# veils_v40.net
KiCad netlist of a schematic drawn in EAGLE
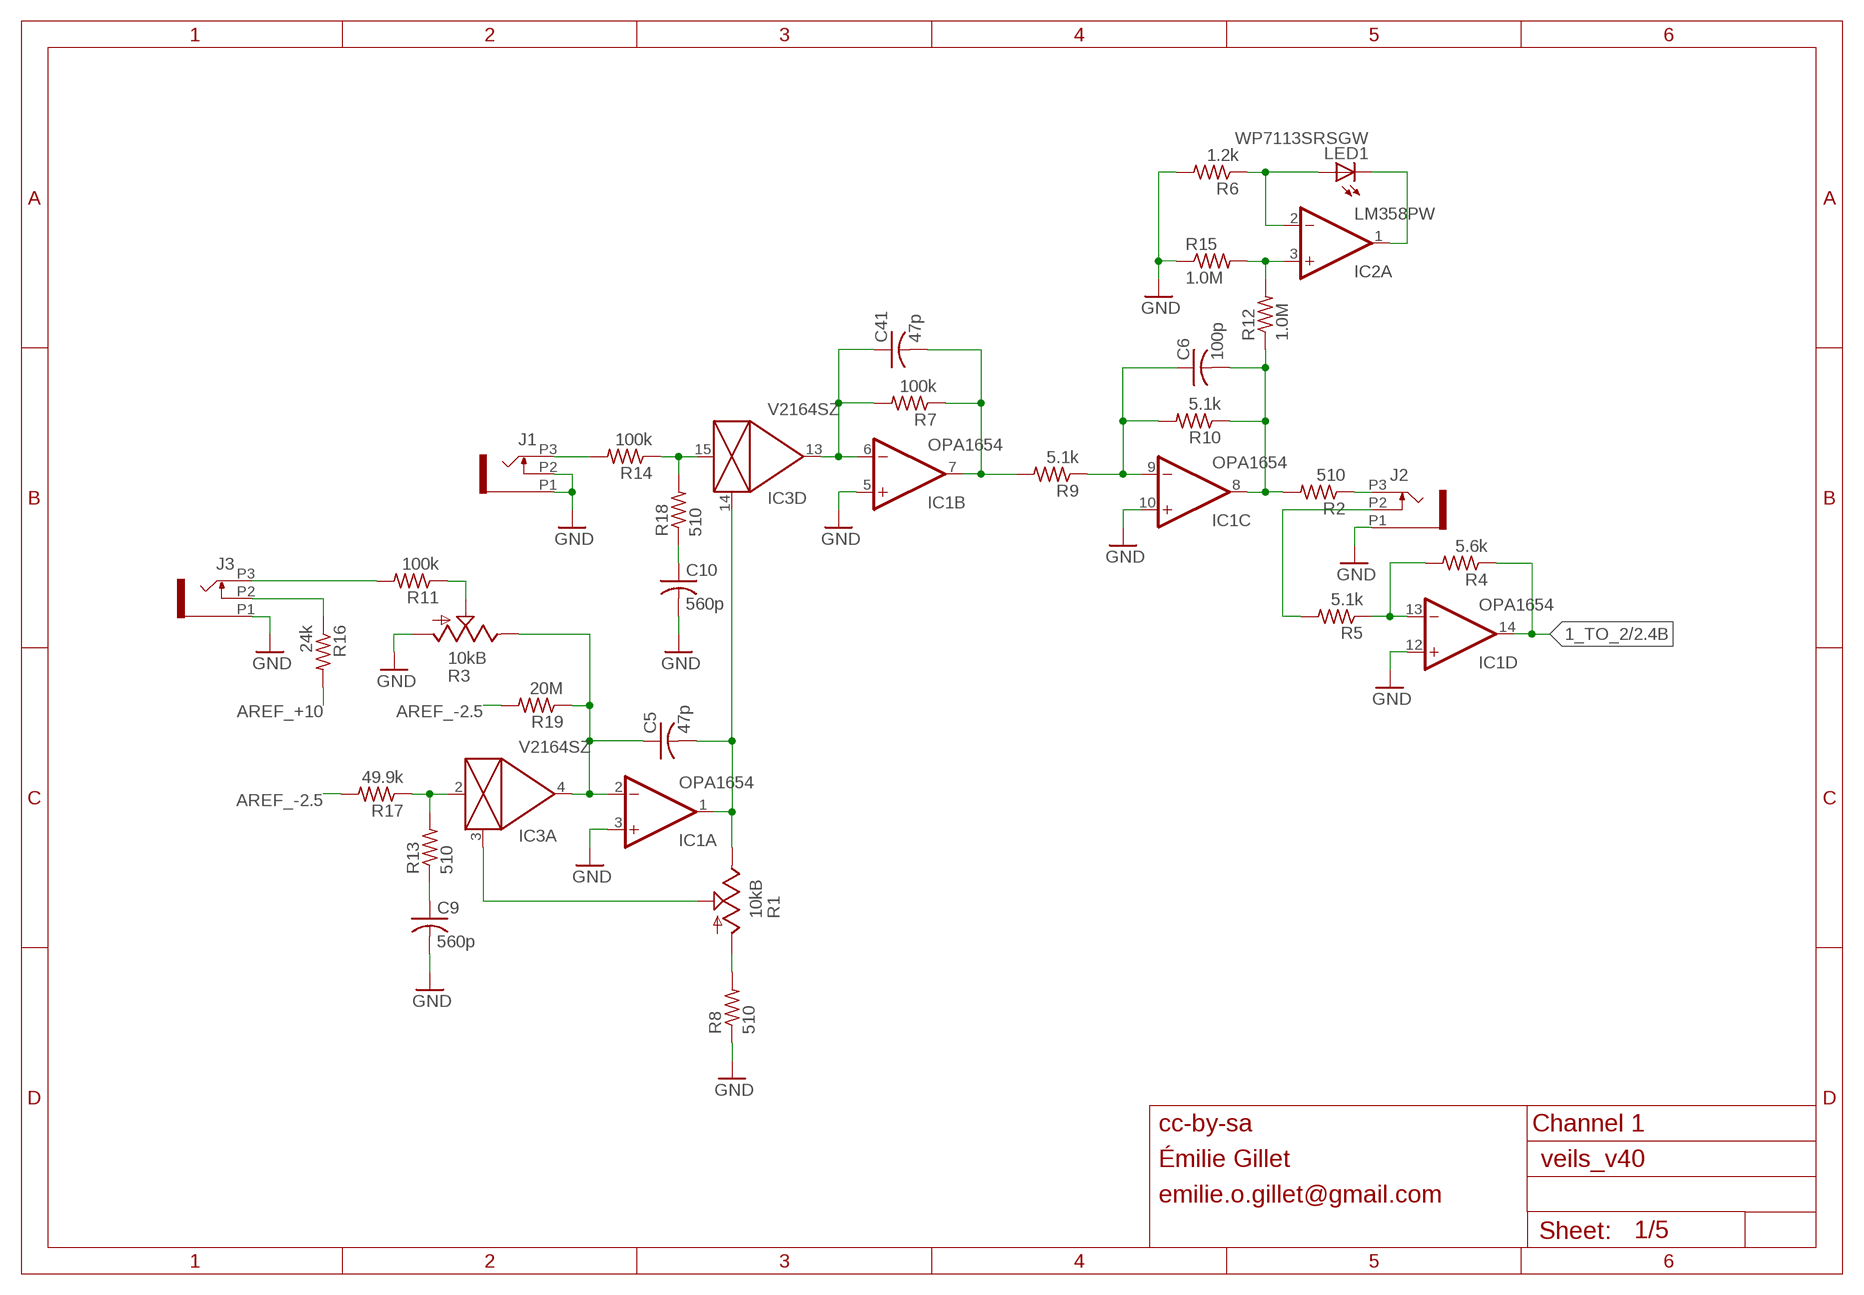
[diagram p0: schematic, sheet 1]
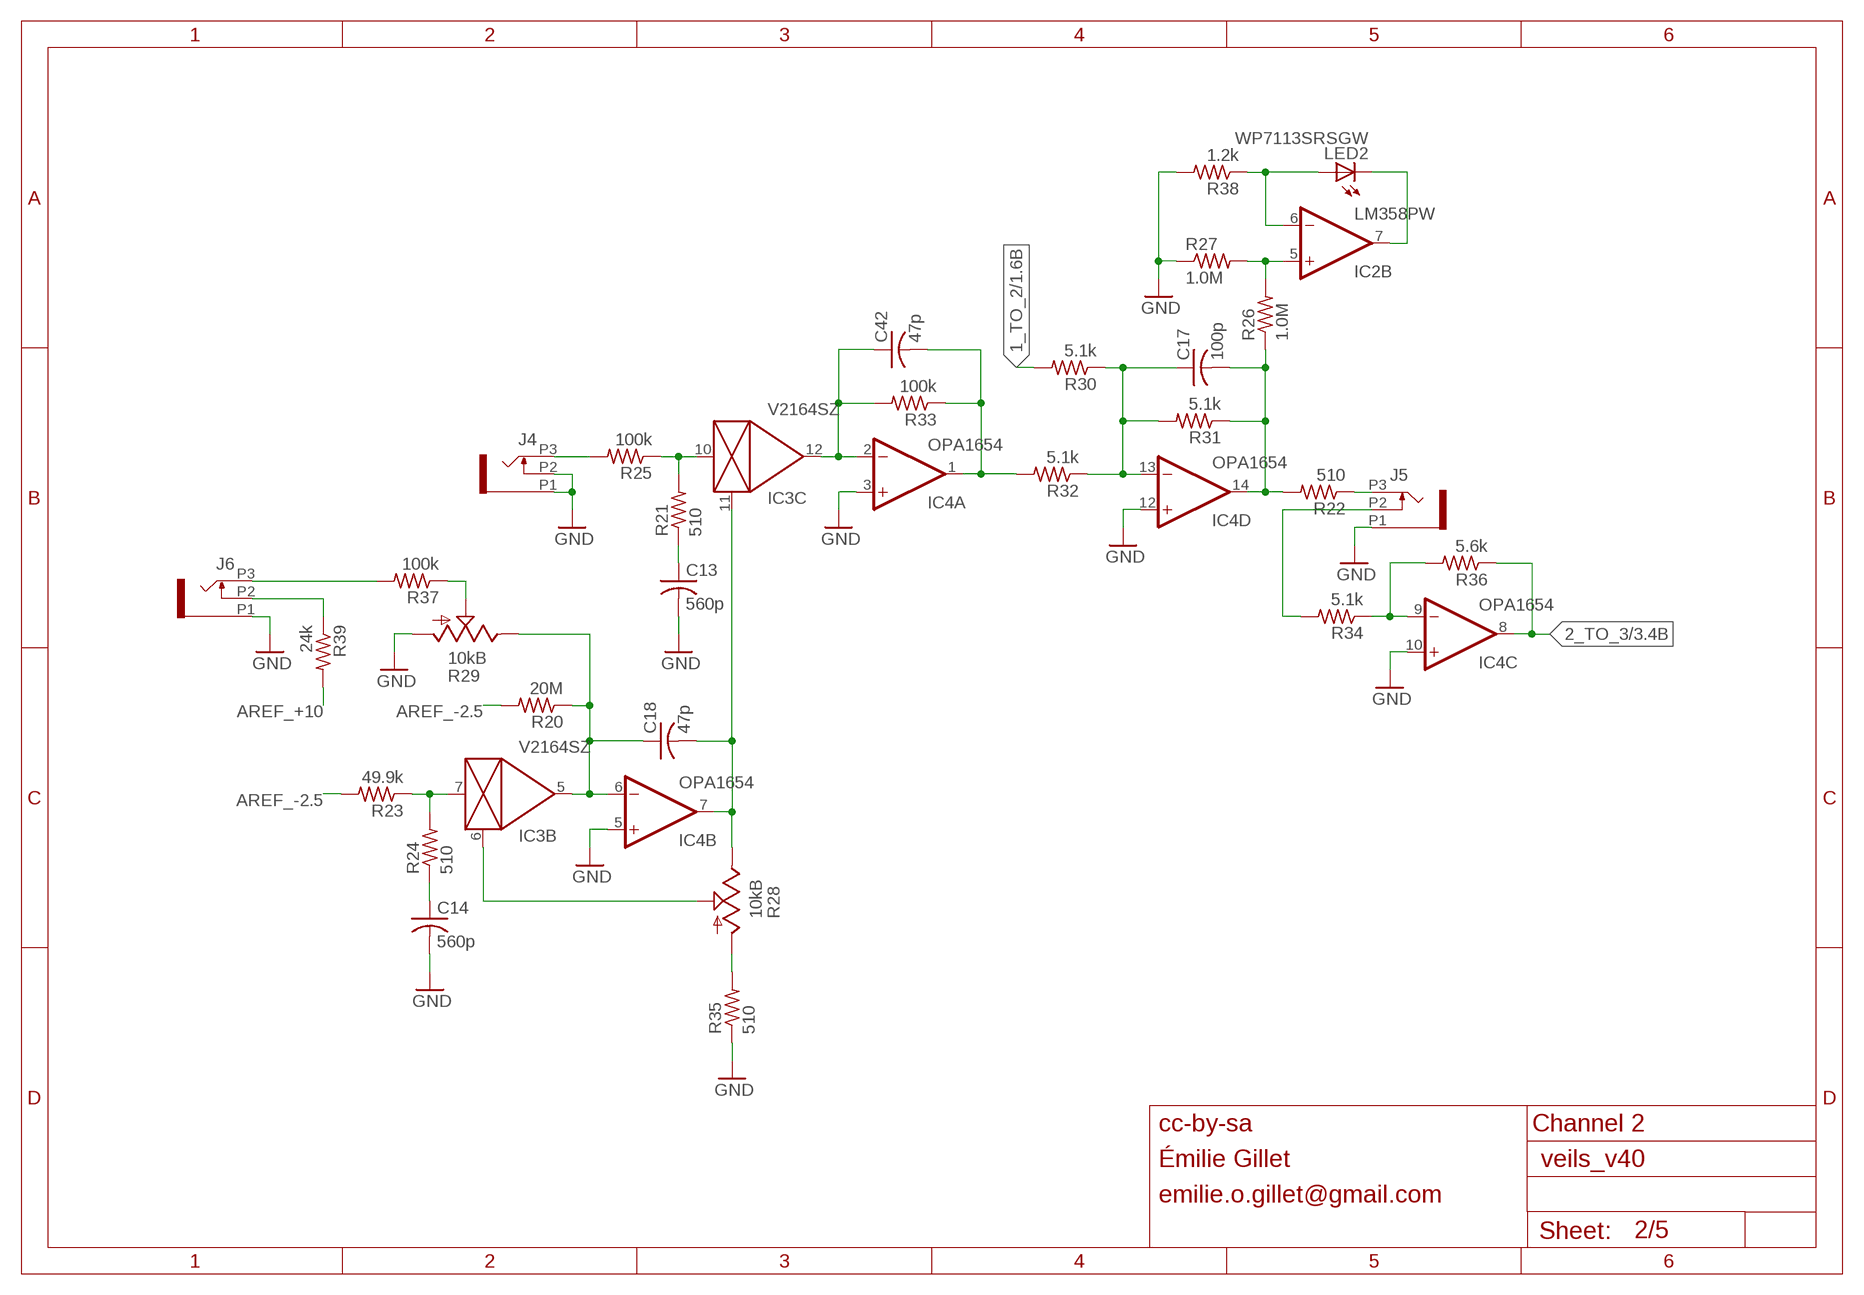
[diagram p1: schematic, sheet 2]
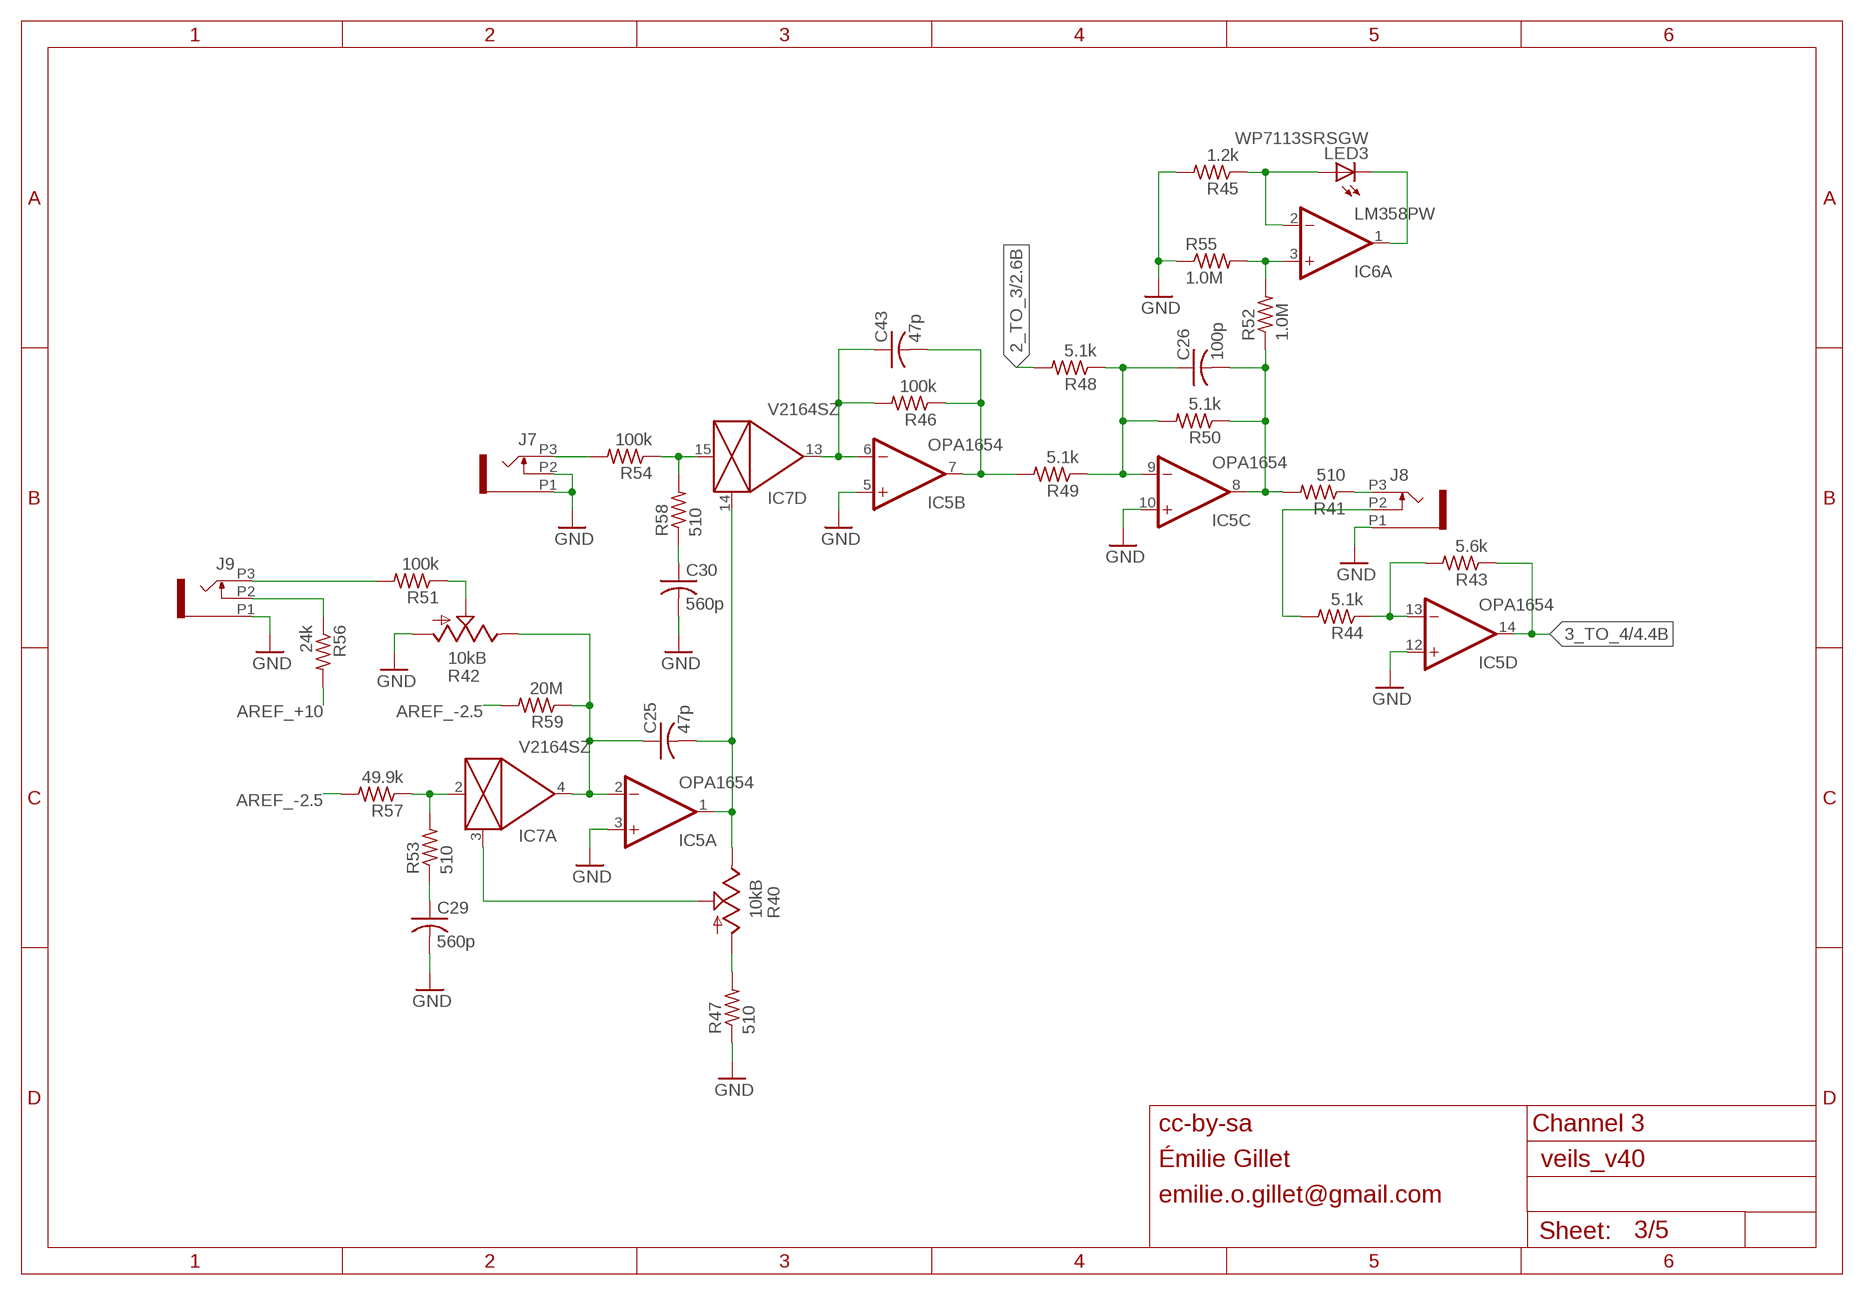
[diagram p2: schematic, sheet 3]
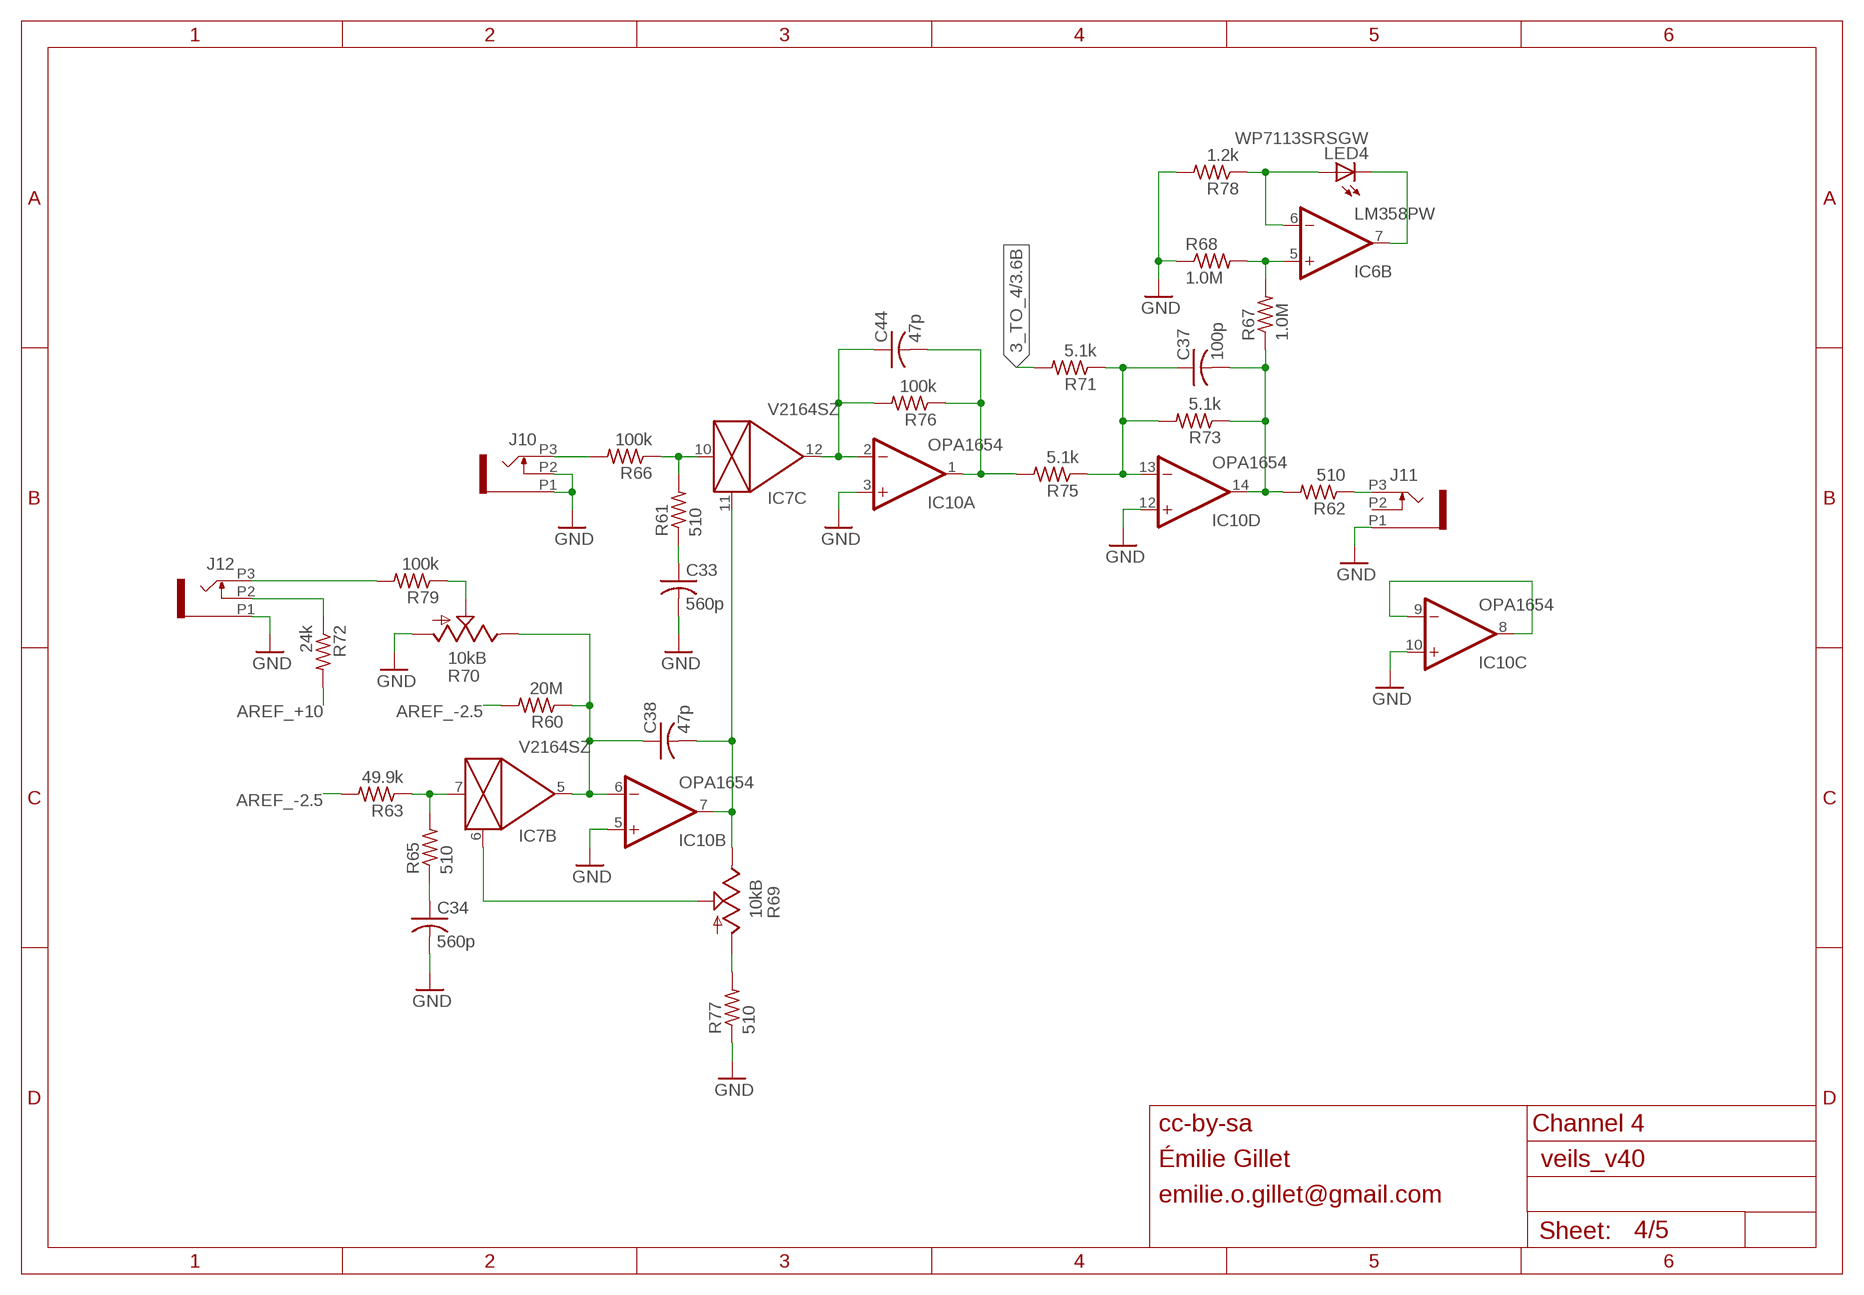
[diagram p3: schematic, sheet 4]
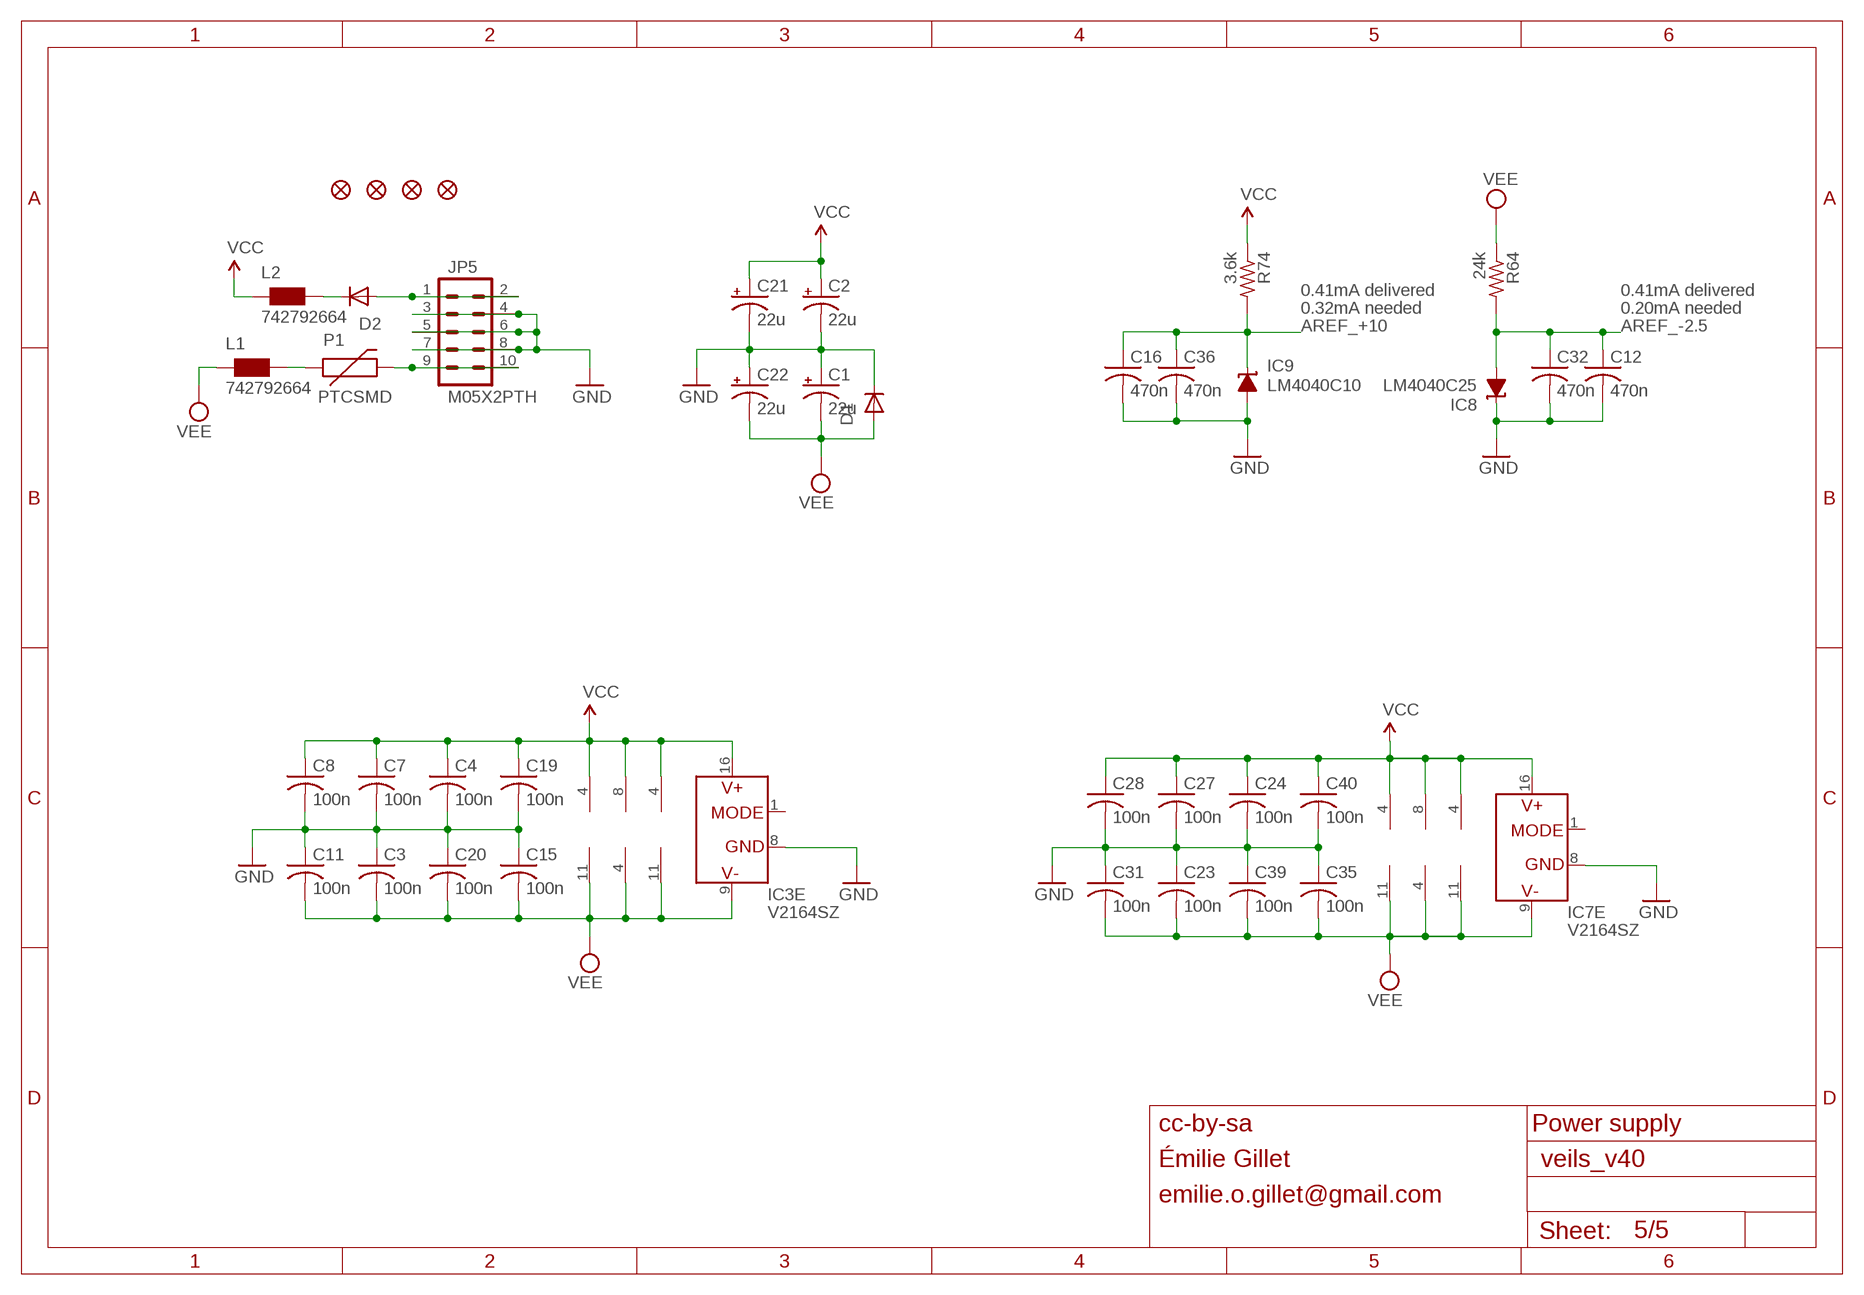
[diagram p4: schematic, sheet 5]

(export (version "E")
  (design (tool "Eeschema 10.0.6"))
  (components
    (comp (ref "C25")
      (value "47p")
      (footprint "eagle-import:C0402")
      (libsource (lib "eagle-import") (part "C-USC0402"))
    )
    (comp (ref "C26")
      (value "100p")
      (footprint "eagle-import:C0402")
      (libsource (lib "eagle-import") (part "C-USC0402"))
    )
    (comp (ref "C29")
      (value "560p")
      (footprint "eagle-import:C0402")
      (libsource (lib "eagle-import") (part "C-USC0402"))
    )
    (comp (ref "C30")
      (value "560p")
      (footprint "eagle-import:C0402")
      (libsource (lib "eagle-import") (part "C-USC0402"))
    )
    (comp (ref "C43")
      (value "47p")
      (footprint "eagle-import:C0402")
      (libsource (lib "eagle-import") (part "C-USC0402"))
    )
    (comp (ref "IC5")
      (value "OPA1654")
      (footprint "eagle-import:TSSOP14")
      (libsource (lib "eagle-import") (part "TL074PW"))
    )
    (comp (ref "IC6")
      (value "LM358PW")
      (footprint "eagle-import:TSSOP8")
      (libsource (lib "eagle-import") (part "TL072PW"))
    )
    (comp (ref "IC7")
      (value "V2164SZ")
      (footprint "eagle-import:SOIC16N")
      (libsource (lib "eagle-import") (part "SSM2164S"))
    )
    (comp (ref "J7")
      (value "PJ301_THONKICONN6")
      (footprint "eagle-import:WQP_PJ_301M6")
      (libsource (lib "eagle-import") (part "PJ301_THONKICONN6"))
    )
    (comp (ref "J8")
      (value "PJ301_THONKICONN6")
      (footprint "eagle-import:WQP_PJ_301M6")
      (libsource (lib "eagle-import") (part "PJ301_THONKICONN6"))
    )
    (comp (ref "J9")
      (value "PJ301_THONKICONN6")
      (footprint "eagle-import:WQP_PJ_301M6")
      (libsource (lib "eagle-import") (part "PJ301_THONKICONN6"))
    )
    (comp (ref "LED3")
      (value "WP7113SRSGW")
      (footprint "eagle-import:LED5MM")
      (libsource (lib "eagle-import") (part "LED5MM"))
    )
    (comp (ref "R40")
      (value "10kB")
      (footprint "eagle-import:ALPS_POT_VERTICAL")
      (libsource (lib "eagle-import") (part "POT_USVERTICAL"))
    )
    (comp (ref "R41")
      (value "510")
      (footprint "eagle-import:R0402")
      (libsource (lib "eagle-import") (part "R-US_R0402"))
    )
    (comp (ref "R42")
      (value "10kB")
      (footprint "eagle-import:ALPS_POT_VERTICAL_PS")
      (libsource (lib "eagle-import") (part "pot-alps_POT_USVERTICAL_PS"))
    )
    (comp (ref "R43")
      (value "5.6k")
      (footprint "eagle-import:R0402")
      (libsource (lib "eagle-import") (part "R-US_R0402"))
    )
    (comp (ref "R44")
      (value "5.1k")
      (footprint "eagle-import:R0402")
      (libsource (lib "eagle-import") (part "R-US_R0402"))
    )
    (comp (ref "R45")
      (value "1.2k")
      (footprint "eagle-import:R0402")
      (libsource (lib "eagle-import") (part "R-US_R0402"))
    )
    (comp (ref "R46")
      (value "100k")
      (footprint "eagle-import:R0402")
      (libsource (lib "eagle-import") (part "R-US_R0402"))
    )
    (comp (ref "R47")
      (value "510")
      (footprint "eagle-import:R0402")
      (libsource (lib "eagle-import") (part "R-US_R0402"))
    )
    (comp (ref "R48")
      (value "5.1k")
      (footprint "eagle-import:R0402")
      (libsource (lib "eagle-import") (part "R-US_R0402"))
    )
    (comp (ref "R49")
      (value "5.1k")
      (footprint "eagle-import:R0402")
      (libsource (lib "eagle-import") (part "R-US_R0402"))
    )
    (comp (ref "R50")
      (value "5.1k")
      (footprint "eagle-import:R0402")
      (libsource (lib "eagle-import") (part "R-US_R0402"))
    )
    (comp (ref "R51")
      (value "100k")
      (footprint "eagle-import:R0402")
      (libsource (lib "eagle-import") (part "R-US_R0402"))
    )
    (comp (ref "R52")
      (value "1.0M")
      (footprint "eagle-import:R0402")
      (libsource (lib "eagle-import") (part "R-US_R0402"))
    )
    (comp (ref "R53")
      (value "510")
      (footprint "eagle-import:R0402")
      (libsource (lib "eagle-import") (part "R-US_R0402"))
    )
    (comp (ref "R54")
      (value "100k")
      (footprint "eagle-import:R0402")
      (libsource (lib "eagle-import") (part "R-US_R0402"))
    )
    (comp (ref "R55")
      (value "1.0M")
      (footprint "eagle-import:R0402")
      (libsource (lib "eagle-import") (part "R-US_R0402"))
    )
    (comp (ref "R56")
      (value "24k")
      (footprint "eagle-import:R0402")
      (libsource (lib "eagle-import") (part "R-US_R0402"))
    )
    (comp (ref "R57")
      (value "49.9k")
      (footprint "eagle-import:R0402")
      (libsource (lib "eagle-import") (part "R-US_R0402"))
    )
    (comp (ref "R58")
      (value "510")
      (footprint "eagle-import:R0402")
      (libsource (lib "eagle-import") (part "R-US_R0402"))
    )
    (comp (ref "R59")
      (value "20M")
      (footprint "eagle-import:R0402")
      (libsource (lib "eagle-import") (part "R-US_R0402"))
    )
    (comp (ref "C33")
      (value "560p")
      (footprint "eagle-import:C0402")
      (libsource (lib "eagle-import") (part "C-USC0402"))
    )
    (comp (ref "C34")
      (value "560p")
      (footprint "eagle-import:C0402")
      (libsource (lib "eagle-import") (part "C-USC0402"))
    )
    (comp (ref "C37")
      (value "100p")
      (footprint "eagle-import:C0402")
      (libsource (lib "eagle-import") (part "C-USC0402"))
    )
    (comp (ref "C38")
      (value "47p")
      (footprint "eagle-import:C0402")
      (libsource (lib "eagle-import") (part "C-USC0402"))
    )
    (comp (ref "C44")
      (value "47p")
      (footprint "eagle-import:C0402")
      (libsource (lib "eagle-import") (part "C-USC0402"))
    )
    (comp (ref "IC10")
      (value "OPA1654")
      (footprint "eagle-import:TSSOP14")
      (libsource (lib "eagle-import") (part "TL074PW"))
    )
    (comp (ref "J10")
      (value "PJ301_THONKICONN6")
      (footprint "eagle-import:WQP_PJ_301M6")
      (libsource (lib "eagle-import") (part "PJ301_THONKICONN6"))
    )
    (comp (ref "J11")
      (value "PJ301_THONKICONN6")
      (footprint "eagle-import:WQP_PJ_301M6")
      (libsource (lib "eagle-import") (part "PJ301_THONKICONN6"))
    )
    (comp (ref "J12")
      (value "PJ301_THONKICONN6")
      (footprint "eagle-import:WQP_PJ_301M6")
      (libsource (lib "eagle-import") (part "PJ301_THONKICONN6"))
    )
    (comp (ref "LED4")
      (value "WP7113SRSGW")
      (footprint "eagle-import:LED5MM")
      (libsource (lib "eagle-import") (part "LED5MM"))
    )
    (comp (ref "R60")
      (value "20M")
      (footprint "eagle-import:R0402")
      (libsource (lib "eagle-import") (part "R-US_R0402"))
    )
    (comp (ref "R61")
      (value "510")
      (footprint "eagle-import:R0402")
      (libsource (lib "eagle-import") (part "R-US_R0402"))
    )
    (comp (ref "R62")
      (value "510")
      (footprint "eagle-import:R0402")
      (libsource (lib "eagle-import") (part "R-US_R0402"))
    )
    (comp (ref "R63")
      (value "49.9k")
      (footprint "eagle-import:R0402")
      (libsource (lib "eagle-import") (part "R-US_R0402"))
    )
    (comp (ref "R65")
      (value "510")
      (footprint "eagle-import:R0402")
      (libsource (lib "eagle-import") (part "R-US_R0402"))
    )
    (comp (ref "R66")
      (value "100k")
      (footprint "eagle-import:R0402")
      (libsource (lib "eagle-import") (part "R-US_R0402"))
    )
    (comp (ref "R67")
      (value "1.0M")
      (footprint "eagle-import:R0402")
      (libsource (lib "eagle-import") (part "R-US_R0402"))
    )
    (comp (ref "R68")
      (value "1.0M")
      (footprint "eagle-import:R0402")
      (libsource (lib "eagle-import") (part "R-US_R0402"))
    )
    (comp (ref "R69")
      (value "10kB")
      (footprint "eagle-import:ALPS_POT_VERTICAL")
      (libsource (lib "eagle-import") (part "POT_USVERTICAL"))
    )
    (comp (ref "R70")
      (value "10kB")
      (footprint "eagle-import:ALPS_POT_VERTICAL_PS")
      (libsource (lib "eagle-import") (part "pot-alps_POT_USVERTICAL_PS"))
    )
    (comp (ref "R71")
      (value "5.1k")
      (footprint "eagle-import:R0402")
      (libsource (lib "eagle-import") (part "R-US_R0402"))
    )
    (comp (ref "R72")
      (value "24k")
      (footprint "eagle-import:R0402")
      (libsource (lib "eagle-import") (part "R-US_R0402"))
    )
    (comp (ref "R73")
      (value "5.1k")
      (footprint "eagle-import:R0402")
      (libsource (lib "eagle-import") (part "R-US_R0402"))
    )
    (comp (ref "R75")
      (value "5.1k")
      (footprint "eagle-import:R0402")
      (libsource (lib "eagle-import") (part "R-US_R0402"))
    )
    (comp (ref "R76")
      (value "100k")
      (footprint "eagle-import:R0402")
      (libsource (lib "eagle-import") (part "R-US_R0402"))
    )
    (comp (ref "R77")
      (value "510")
      (footprint "eagle-import:R0402")
      (libsource (lib "eagle-import") (part "R-US_R0402"))
    )
    (comp (ref "R78")
      (value "1.2k")
      (footprint "eagle-import:R0402")
      (libsource (lib "eagle-import") (part "R-US_R0402"))
    )
    (comp (ref "R79")
      (value "100k")
      (footprint "eagle-import:R0402")
      (libsource (lib "eagle-import") (part "R-US_R0402"))
    )
    (comp (ref "C13")
      (value "560p")
      (footprint "eagle-import:C0402")
      (libsource (lib "eagle-import") (part "C-USC0402"))
    )
    (comp (ref "C14")
      (value "560p")
      (footprint "eagle-import:C0402")
      (libsource (lib "eagle-import") (part "C-USC0402"))
    )
    (comp (ref "C17")
      (value "100p")
      (footprint "eagle-import:C0402")
      (libsource (lib "eagle-import") (part "C-USC0402"))
    )
    (comp (ref "C18")
      (value "47p")
      (footprint "eagle-import:C0402")
      (libsource (lib "eagle-import") (part "C-USC0402"))
    )
    (comp (ref "C42")
      (value "47p")
      (footprint "eagle-import:C0402")
      (libsource (lib "eagle-import") (part "C-USC0402"))
    )
    (comp (ref "IC2")
      (value "LM358PW")
      (footprint "eagle-import:TSSOP8")
      (libsource (lib "eagle-import") (part "TL072PW"))
    )
    (comp (ref "IC3")
      (value "V2164SZ")
      (footprint "eagle-import:SOIC16N")
      (libsource (lib "eagle-import") (part "SSM2164S"))
    )
    (comp (ref "IC4")
      (value "OPA1654")
      (footprint "eagle-import:TSSOP14")
      (libsource (lib "eagle-import") (part "TL074PW"))
    )
    (comp (ref "J4")
      (value "PJ301_THONKICONN6")
      (footprint "eagle-import:WQP_PJ_301M6")
      (libsource (lib "eagle-import") (part "PJ301_THONKICONN6"))
    )
    (comp (ref "J5")
      (value "PJ301_THONKICONN6")
      (footprint "eagle-import:WQP_PJ_301M6")
      (libsource (lib "eagle-import") (part "PJ301_THONKICONN6"))
    )
    (comp (ref "J6")
      (value "PJ301_THONKICONN6")
      (footprint "eagle-import:WQP_PJ_301M6")
      (libsource (lib "eagle-import") (part "PJ301_THONKICONN6"))
    )
    (comp (ref "LED2")
      (value "WP7113SRSGW")
      (footprint "eagle-import:LED5MM")
      (libsource (lib "eagle-import") (part "LED5MM"))
    )
    (comp (ref "R20")
      (value "20M")
      (footprint "eagle-import:R0402")
      (libsource (lib "eagle-import") (part "R-US_R0402"))
    )
    (comp (ref "R21")
      (value "510")
      (footprint "eagle-import:R0402")
      (libsource (lib "eagle-import") (part "R-US_R0402"))
    )
    (comp (ref "R22")
      (value "510")
      (footprint "eagle-import:R0402")
      (libsource (lib "eagle-import") (part "R-US_R0402"))
    )
    (comp (ref "R23")
      (value "49.9k")
      (footprint "eagle-import:R0402")
      (libsource (lib "eagle-import") (part "R-US_R0402"))
    )
    (comp (ref "R24")
      (value "510")
      (footprint "eagle-import:R0402")
      (libsource (lib "eagle-import") (part "R-US_R0402"))
    )
    (comp (ref "R25")
      (value "100k")
      (footprint "eagle-import:R0402")
      (libsource (lib "eagle-import") (part "R-US_R0402"))
    )
    (comp (ref "R26")
      (value "1.0M")
      (footprint "eagle-import:R0402")
      (libsource (lib "eagle-import") (part "R-US_R0402"))
    )
    (comp (ref "R27")
      (value "1.0M")
      (footprint "eagle-import:R0402")
      (libsource (lib "eagle-import") (part "R-US_R0402"))
    )
    (comp (ref "R28")
      (value "10kB")
      (footprint "eagle-import:ALPS_POT_VERTICAL")
      (libsource (lib "eagle-import") (part "POT_USVERTICAL"))
    )
    (comp (ref "R29")
      (value "10kB")
      (footprint "eagle-import:ALPS_POT_VERTICAL_PS")
      (libsource (lib "eagle-import") (part "pot-alps_POT_USVERTICAL_PS"))
    )
    (comp (ref "R30")
      (value "5.1k")
      (footprint "eagle-import:R0402")
      (libsource (lib "eagle-import") (part "R-US_R0402"))
    )
    (comp (ref "R31")
      (value "5.1k")
      (footprint "eagle-import:R0402")
      (libsource (lib "eagle-import") (part "R-US_R0402"))
    )
    (comp (ref "R32")
      (value "5.1k")
      (footprint "eagle-import:R0402")
      (libsource (lib "eagle-import") (part "R-US_R0402"))
    )
    (comp (ref "R33")
      (value "100k")
      (footprint "eagle-import:R0402")
      (libsource (lib "eagle-import") (part "R-US_R0402"))
    )
    (comp (ref "R34")
      (value "5.1k")
      (footprint "eagle-import:R0402")
      (libsource (lib "eagle-import") (part "R-US_R0402"))
    )
    (comp (ref "R35")
      (value "510")
      (footprint "eagle-import:R0402")
      (libsource (lib "eagle-import") (part "R-US_R0402"))
    )
    (comp (ref "R36")
      (value "5.6k")
      (footprint "eagle-import:R0402")
      (libsource (lib "eagle-import") (part "R-US_R0402"))
    )
    (comp (ref "R37")
      (value "100k")
      (footprint "eagle-import:R0402")
      (libsource (lib "eagle-import") (part "R-US_R0402"))
    )
    (comp (ref "R38")
      (value "1.2k")
      (footprint "eagle-import:R0402")
      (libsource (lib "eagle-import") (part "R-US_R0402"))
    )
    (comp (ref "R39")
      (value "24k")
      (footprint "eagle-import:R0402")
      (libsource (lib "eagle-import") (part "R-US_R0402"))
    )
    (comp (ref "C1")
      (value "22u")
      (footprint "eagle-import:PANASONIC_B")
      (libsource (lib "eagle-import") (part "CPOL-USB"))
    )
    (comp (ref "C2")
      (value "22u")
      (footprint "eagle-import:PANASONIC_B")
      (libsource (lib "eagle-import") (part "CPOL-USB"))
    )
    (comp (ref "C3")
      (value "100n")
      (footprint "eagle-import:C0402")
      (libsource (lib "eagle-import") (part "C-USC0402"))
    )
    (comp (ref "C4")
      (value "100n")
      (footprint "eagle-import:C0402")
      (libsource (lib "eagle-import") (part "C-USC0402"))
    )
    (comp (ref "C7")
      (value "100n")
      (footprint "eagle-import:C0402")
      (libsource (lib "eagle-import") (part "C-USC0402"))
    )
    (comp (ref "C8")
      (value "100n")
      (footprint "eagle-import:C0402")
      (libsource (lib "eagle-import") (part "C-USC0402"))
    )
    (comp (ref "C11")
      (value "100n")
      (footprint "eagle-import:C0402")
      (libsource (lib "eagle-import") (part "C-USC0402"))
    )
    (comp (ref "C12")
      (value "470n")
      (footprint "eagle-import:C0402")
      (libsource (lib "eagle-import") (part "C-USC0402"))
    )
    (comp (ref "C15")
      (value "100n")
      (footprint "eagle-import:C0402")
      (libsource (lib "eagle-import") (part "C-USC0402"))
    )
    (comp (ref "C16")
      (value "470n")
      (footprint "eagle-import:C0402")
      (libsource (lib "eagle-import") (part "C-USC0402"))
    )
    (comp (ref "C19")
      (value "100n")
      (footprint "eagle-import:C0402")
      (libsource (lib "eagle-import") (part "C-USC0402"))
    )
    (comp (ref "C20")
      (value "100n")
      (footprint "eagle-import:C0402")
      (libsource (lib "eagle-import") (part "C-USC0402"))
    )
    (comp (ref "C21")
      (value "22u")
      (footprint "eagle-import:PANASONIC_B")
      (libsource (lib "eagle-import") (part "CPOL-USB"))
    )
    (comp (ref "C22")
      (value "22u")
      (footprint "eagle-import:PANASONIC_B")
      (libsource (lib "eagle-import") (part "CPOL-USB"))
    )
    (comp (ref "C23")
      (value "100n")
      (footprint "eagle-import:C0402")
      (libsource (lib "eagle-import") (part "C-USC0402"))
    )
    (comp (ref "C24")
      (value "100n")
      (footprint "eagle-import:C0402")
      (libsource (lib "eagle-import") (part "C-USC0402"))
    )
    (comp (ref "C27")
      (value "100n")
      (footprint "eagle-import:C0402")
      (libsource (lib "eagle-import") (part "C-USC0402"))
    )
    (comp (ref "C28")
      (value "100n")
      (footprint "eagle-import:C0402")
      (libsource (lib "eagle-import") (part "C-USC0402"))
    )
    (comp (ref "C31")
      (value "100n")
      (footprint "eagle-import:C0402")
      (libsource (lib "eagle-import") (part "C-USC0402"))
    )
    (comp (ref "C32")
      (value "470n")
      (footprint "eagle-import:C0402")
      (libsource (lib "eagle-import") (part "C-USC0402"))
    )
    (comp (ref "C35")
      (value "100n")
      (footprint "eagle-import:C0402")
      (libsource (lib "eagle-import") (part "C-USC0402"))
    )
    (comp (ref "C36")
      (value "470n")
      (footprint "eagle-import:C0402")
      (libsource (lib "eagle-import") (part "C-USC0402"))
    )
    (comp (ref "C39")
      (value "100n")
      (footprint "eagle-import:C0402")
      (libsource (lib "eagle-import") (part "C-USC0402"))
    )
    (comp (ref "C40")
      (value "100n")
      (footprint "eagle-import:C0402")
      (libsource (lib "eagle-import") (part "C-USC0402"))
    )
    (comp (ref "D1")
      (value "1N5819HW")
      (footprint "eagle-import:SOD123")
      (libsource (lib "eagle-import") (part "DIODE-SOD123"))
    )
    (comp (ref "D2")
      (value "1N5819HW")
      (footprint "eagle-import:SOD123")
      (libsource (lib "eagle-import") (part "DIODE-SOD123"))
    )
    (comp (ref "IC1")
      (value "OPA1654")
      (footprint "eagle-import:TSSOP14")
      (libsource (lib "eagle-import") (part "TL074PW"))
    )
    (comp (ref "IC8")
      (value "LM4040C25")
      (footprint "eagle-import:DBZ_R-PDSO-G3")
      (libsource (lib "eagle-import") (part "LM4041DBZB12"))
    )
    (comp (ref "IC9")
      (value "LM4040C10")
      (footprint "eagle-import:DBZ_R-PDSO-G3")
      (libsource (lib "eagle-import") (part "LM4041DBZB12"))
    )
    (comp (ref "JP1")
      (value "FIDUCIAL1X2")
      (footprint "eagle-import:FIDUCIAL-1X2")
      (libsource (lib "eagle-import") (part "FIDUCIAL1X2"))
    )
    (comp (ref "JP2")
      (value "FIDUCIAL1X2")
      (footprint "eagle-import:FIDUCIAL-1X2")
      (libsource (lib "eagle-import") (part "FIDUCIAL1X2"))
    )
    (comp (ref "JP3")
      (value "FIDUCIAL1X2")
      (footprint "eagle-import:FIDUCIAL-1X2")
      (libsource (lib "eagle-import") (part "FIDUCIAL1X2"))
    )
    (comp (ref "JP4")
      (value "FIDUCIAL1X2")
      (footprint "eagle-import:FIDUCIAL-1X2")
      (libsource (lib "eagle-import") (part "FIDUCIAL1X2"))
    )
    (comp (ref "JP5")
      (value "M05X2PTH")
      (footprint "eagle-import:AVR_ICSP")
      (libsource (lib "eagle-import") (part "M05X2PTH"))
    )
    (comp (ref "L1")
      (value "742792664")
      (footprint "eagle-import:0603")
      (libsource (lib "eagle-import") (part "WE-CBF_0603"))
    )
    (comp (ref "L2")
      (value "742792664")
      (footprint "eagle-import:0603")
      (libsource (lib "eagle-import") (part "WE-CBF_0603"))
    )
    (comp (ref "P1")
      (value "PTCSMD")
      (footprint "eagle-import:PTC-1206")
      (libsource (lib "eagle-import") (part "PTCSMD"))
    )
    (comp (ref "R64")
      (value "24k")
      (footprint "eagle-import:R0402")
      (libsource (lib "eagle-import") (part "R-US_R0402"))
    )
    (comp (ref "R74")
      (value "3.6k")
      (footprint "eagle-import:R0402")
      (libsource (lib "eagle-import") (part "R-US_R0402"))
    )
    (comp (ref "C5")
      (value "47p")
      (footprint "eagle-import:C0402")
      (libsource (lib "eagle-import") (part "C-USC0402"))
    )
    (comp (ref "C6")
      (value "100p")
      (footprint "eagle-import:C0402")
      (libsource (lib "eagle-import") (part "C-USC0402"))
    )
    (comp (ref "C9")
      (value "560p")
      (footprint "eagle-import:C0402")
      (libsource (lib "eagle-import") (part "C-USC0402"))
    )
    (comp (ref "C10")
      (value "560p")
      (footprint "eagle-import:C0402")
      (libsource (lib "eagle-import") (part "C-USC0402"))
    )
    (comp (ref "C41")
      (value "47p")
      (footprint "eagle-import:C0402")
      (libsource (lib "eagle-import") (part "C-USC0402"))
    )
    (comp (ref "J1")
      (value "PJ301_THONKICONN6")
      (footprint "eagle-import:WQP_PJ_301M6")
      (libsource (lib "eagle-import") (part "PJ301_THONKICONN6"))
    )
    (comp (ref "J2")
      (value "PJ301_THONKICONN6")
      (footprint "eagle-import:WQP_PJ_301M6")
      (libsource (lib "eagle-import") (part "PJ301_THONKICONN6"))
    )
    (comp (ref "J3")
      (value "PJ301_THONKICONN6")
      (footprint "eagle-import:WQP_PJ_301M6")
      (libsource (lib "eagle-import") (part "PJ301_THONKICONN6"))
    )
    (comp (ref "LED1")
      (value "WP7113SRSGW")
      (footprint "eagle-import:LED5MM")
      (libsource (lib "eagle-import") (part "LED5MM"))
    )
    (comp (ref "R1")
      (value "10kB")
      (footprint "eagle-import:ALPS_POT_VERTICAL")
      (libsource (lib "eagle-import") (part "POT_USVERTICAL"))
    )
    (comp (ref "R2")
      (value "510")
      (footprint "eagle-import:R0402")
      (libsource (lib "eagle-import") (part "R-US_R0402"))
    )
    (comp (ref "R3")
      (value "10kB")
      (footprint "eagle-import:ALPS_POT_VERTICAL_PS")
      (libsource (lib "eagle-import") (part "pot-alps_POT_USVERTICAL_PS"))
    )
    (comp (ref "R4")
      (value "5.6k")
      (footprint "eagle-import:R0402")
      (libsource (lib "eagle-import") (part "R-US_R0402"))
    )
    (comp (ref "R5")
      (value "5.1k")
      (footprint "eagle-import:R0402")
      (libsource (lib "eagle-import") (part "R-US_R0402"))
    )
    (comp (ref "R6")
      (value "1.2k")
      (footprint "eagle-import:R0402")
      (libsource (lib "eagle-import") (part "R-US_R0402"))
    )
    (comp (ref "R7")
      (value "100k")
      (footprint "eagle-import:R0402")
      (libsource (lib "eagle-import") (part "R-US_R0402"))
    )
    (comp (ref "R8")
      (value "510")
      (footprint "eagle-import:R0402")
      (libsource (lib "eagle-import") (part "R-US_R0402"))
    )
    (comp (ref "R9")
      (value "5.1k")
      (footprint "eagle-import:R0402")
      (libsource (lib "eagle-import") (part "R-US_R0402"))
    )
    (comp (ref "R10")
      (value "5.1k")
      (footprint "eagle-import:R0402")
      (libsource (lib "eagle-import") (part "R-US_R0402"))
    )
    (comp (ref "R11")
      (value "100k")
      (footprint "eagle-import:R0402")
      (libsource (lib "eagle-import") (part "R-US_R0402"))
    )
    (comp (ref "R12")
      (value "1.0M")
      (footprint "eagle-import:R0402")
      (libsource (lib "eagle-import") (part "R-US_R0402"))
    )
    (comp (ref "R13")
      (value "510")
      (footprint "eagle-import:R0402")
      (libsource (lib "eagle-import") (part "R-US_R0402"))
    )
    (comp (ref "R14")
      (value "100k")
      (footprint "eagle-import:R0402")
      (libsource (lib "eagle-import") (part "R-US_R0402"))
    )
    (comp (ref "R15")
      (value "1.0M")
      (footprint "eagle-import:R0402")
      (libsource (lib "eagle-import") (part "R-US_R0402"))
    )
    (comp (ref "R16")
      (value "24k")
      (footprint "eagle-import:R0402")
      (libsource (lib "eagle-import") (part "R-US_R0402"))
    )
    (comp (ref "R17")
      (value "49.9k")
      (footprint "eagle-import:R0402")
      (libsource (lib "eagle-import") (part "R-US_R0402"))
    )
    (comp (ref "R18")
      (value "510")
      (footprint "eagle-import:R0402")
      (libsource (lib "eagle-import") (part "R-US_R0402"))
    )
    (comp (ref "R19")
      (value "20M")
      (footprint "eagle-import:R0402")
      (libsource (lib "eagle-import") (part "R-US_R0402"))
    )
  )
  (nets
    (net (code "1") (name "1_TO_2") (class "Default")
      (node (ref "IC1") (pin "14") (pinfunction "OUT_14") (pintype "output"))
      (node (ref "R30") (pin "2") (pinfunction "2_2") (pintype "passive"))
      (node (ref "R4") (pin "1") (pinfunction "1_1") (pintype "passive"))
    )
    (net (code "2") (name "2_TO_3") (class "Default")
      (node (ref "IC4") (pin "8") (pinfunction "OUT_8") (pintype "output"))
      (node (ref "R36") (pin "1") (pinfunction "1_1") (pintype "passive"))
      (node (ref "R48") (pin "2") (pinfunction "2_2") (pintype "passive"))
    )
    (net (code "3") (name "3_TO_4") (class "Default")
      (node (ref "IC5") (pin "14") (pinfunction "OUT_14") (pintype "output"))
      (node (ref "R43") (pin "1") (pinfunction "1_1") (pintype "passive"))
      (node (ref "R71") (pin "2") (pinfunction "2_2") (pintype "passive"))
    )
    (net (code "4") (name "AREF_+10") (class "Default")
      (node (ref "C16") (pin "1") (pinfunction "1_1") (pintype "passive"))
      (node (ref "C36") (pin "1") (pinfunction "1_1") (pintype "passive"))
      (node (ref "IC9") (pin "1") (pinfunction "C_1") (pintype "passive"))
      (node (ref "R16") (pin "2") (pinfunction "2_2") (pintype "passive"))
      (node (ref "R39") (pin "2") (pinfunction "2_2") (pintype "passive"))
      (node (ref "R56") (pin "2") (pinfunction "2_2") (pintype "passive"))
      (node (ref "R72") (pin "2") (pinfunction "2_2") (pintype "passive"))
      (node (ref "R74") (pin "2") (pinfunction "2_2") (pintype "passive"))
    )
    (net (code "5") (name "AREF_-2.5") (class "Default")
      (node (ref "C12") (pin "1") (pinfunction "1_1") (pintype "passive"))
      (node (ref "C32") (pin "1") (pinfunction "1_1") (pintype "passive"))
      (node (ref "IC8") (pin "2") (pinfunction "A_2") (pintype "passive"))
      (node (ref "R17") (pin "2") (pinfunction "2_2") (pintype "passive"))
      (node (ref "R19") (pin "2") (pinfunction "2_2") (pintype "passive"))
      (node (ref "R20") (pin "2") (pinfunction "2_2") (pintype "passive"))
      (node (ref "R23") (pin "2") (pinfunction "2_2") (pintype "passive"))
      (node (ref "R57") (pin "2") (pinfunction "2_2") (pintype "passive"))
      (node (ref "R59") (pin "2") (pinfunction "2_2") (pintype "passive"))
      (node (ref "R60") (pin "2") (pinfunction "2_2") (pintype "passive"))
      (node (ref "R63") (pin "2") (pinfunction "2_2") (pintype "passive"))
      (node (ref "R64") (pin "2") (pinfunction "2_2") (pintype "passive"))
    )
    (net (code "6") (name "GND") (class "Default")
      (node (ref "C1") (pin "+") (pinfunction "+_+") (pintype "passive"))
      (node (ref "C10") (pin "2") (pinfunction "2_2") (pintype "passive"))
      (node (ref "C11") (pin "1") (pinfunction "1_1") (pintype "passive"))
      (node (ref "C12") (pin "2") (pinfunction "2_2") (pintype "passive"))
      (node (ref "C13") (pin "2") (pinfunction "2_2") (pintype "passive"))
      (node (ref "C14") (pin "2") (pinfunction "2_2") (pintype "passive"))
      (node (ref "C15") (pin "1") (pinfunction "1_1") (pintype "passive"))
      (node (ref "C16") (pin "2") (pinfunction "2_2") (pintype "passive"))
      (node (ref "C19") (pin "2") (pinfunction "2_2") (pintype "passive"))
      (node (ref "C2") (pin "-") (pinfunction "-_-") (pintype "passive"))
      (node (ref "C20") (pin "1") (pinfunction "1_1") (pintype "passive"))
      (node (ref "C21") (pin "-") (pinfunction "-_-") (pintype "passive"))
      (node (ref "C22") (pin "+") (pinfunction "+_+") (pintype "passive"))
      (node (ref "C23") (pin "1") (pinfunction "1_1") (pintype "passive"))
      (node (ref "C24") (pin "2") (pinfunction "2_2") (pintype "passive"))
      (node (ref "C27") (pin "2") (pinfunction "2_2") (pintype "passive"))
      (node (ref "C28") (pin "2") (pinfunction "2_2") (pintype "passive"))
      (node (ref "C29") (pin "2") (pinfunction "2_2") (pintype "passive"))
      (node (ref "C3") (pin "1") (pinfunction "1_1") (pintype "passive"))
      (node (ref "C30") (pin "2") (pinfunction "2_2") (pintype "passive"))
      (node (ref "C31") (pin "1") (pinfunction "1_1") (pintype "passive"))
      (node (ref "C32") (pin "2") (pinfunction "2_2") (pintype "passive"))
      (node (ref "C33") (pin "2") (pinfunction "2_2") (pintype "passive"))
      (node (ref "C34") (pin "2") (pinfunction "2_2") (pintype "passive"))
      (node (ref "C35") (pin "1") (pinfunction "1_1") (pintype "passive"))
      (node (ref "C36") (pin "2") (pinfunction "2_2") (pintype "passive"))
      (node (ref "C39") (pin "1") (pinfunction "1_1") (pintype "passive"))
      (node (ref "C4") (pin "2") (pinfunction "2_2") (pintype "passive"))
      (node (ref "C40") (pin "2") (pinfunction "2_2") (pintype "passive"))
      (node (ref "C7") (pin "2") (pinfunction "2_2") (pintype "passive"))
      (node (ref "C8") (pin "2") (pinfunction "2_2") (pintype "passive"))
      (node (ref "C9") (pin "2") (pinfunction "2_2") (pintype "passive"))
      (node (ref "D1") (pin "C") (pinfunction "C_C") (pintype "passive"))
      (node (ref "IC1") (pin "10") (pinfunction "+IN_10") (pintype "input"))
      (node (ref "IC1") (pin "12") (pinfunction "+IN_12") (pintype "input"))
      (node (ref "IC1") (pin "3") (pinfunction "+IN_3") (pintype "input"))
      (node (ref "IC1") (pin "5") (pinfunction "+IN_5") (pintype "input"))
      (node (ref "IC10") (pin "10") (pinfunction "+IN_10") (pintype "input"))
      (node (ref "IC10") (pin "12") (pinfunction "+IN_12") (pintype "input"))
      (node (ref "IC10") (pin "3") (pinfunction "+IN_3") (pintype "input"))
      (node (ref "IC10") (pin "5") (pinfunction "+IN_5") (pintype "input"))
      (node (ref "IC3") (pin "8") (pinfunction "GND_8") (pintype "power_in"))
      (node (ref "IC4") (pin "10") (pinfunction "+IN_10") (pintype "input"))
      (node (ref "IC4") (pin "12") (pinfunction "+IN_12") (pintype "input"))
      (node (ref "IC4") (pin "3") (pinfunction "+IN_3") (pintype "input"))
      (node (ref "IC4") (pin "5") (pinfunction "+IN_5") (pintype "input"))
      (node (ref "IC5") (pin "10") (pinfunction "+IN_10") (pintype "input"))
      (node (ref "IC5") (pin "12") (pinfunction "+IN_12") (pintype "input"))
      (node (ref "IC5") (pin "3") (pinfunction "+IN_3") (pintype "input"))
      (node (ref "IC5") (pin "5") (pinfunction "+IN_5") (pintype "input"))
      (node (ref "IC7") (pin "8") (pinfunction "GND_8") (pintype "power_in"))
      (node (ref "IC8") (pin "1") (pinfunction "C_1") (pintype "passive"))
      (node (ref "IC9") (pin "2") (pinfunction "A_2") (pintype "passive"))
      (node (ref "J1") (pin "P1") (pinfunction "1_P1") (pintype "passive"))
      (node (ref "J1") (pin "P2") (pinfunction "2_P2") (pintype "passive"))
      (node (ref "J10") (pin "P1") (pinfunction "1_P1") (pintype "passive"))
      (node (ref "J10") (pin "P2") (pinfunction "2_P2") (pintype "passive"))
      (node (ref "J11") (pin "P1") (pinfunction "1_P1") (pintype "passive"))
      (node (ref "J12") (pin "P1") (pinfunction "1_P1") (pintype "passive"))
      (node (ref "J2") (pin "P1") (pinfunction "1_P1") (pintype "passive"))
      (node (ref "J3") (pin "P1") (pinfunction "1_P1") (pintype "passive"))
      (node (ref "J4") (pin "P1") (pinfunction "1_P1") (pintype "passive"))
      (node (ref "J4") (pin "P2") (pinfunction "2_P2") (pintype "passive"))
      (node (ref "J5") (pin "P1") (pinfunction "1_P1") (pintype "passive"))
      (node (ref "J6") (pin "P1") (pinfunction "1_P1") (pintype "passive"))
      (node (ref "J7") (pin "P1") (pinfunction "1_P1") (pintype "passive"))
      (node (ref "J7") (pin "P2") (pinfunction "2_P2") (pintype "passive"))
      (node (ref "J8") (pin "P1") (pinfunction "1_P1") (pintype "passive"))
      (node (ref "J9") (pin "P1") (pinfunction "1_P1") (pintype "passive"))
      (node (ref "JP5") (pin "3") (pinfunction "3_3") (pintype "passive"))
      (node (ref "JP5") (pin "4") (pinfunction "4_4") (pintype "passive"))
      (node (ref "JP5") (pin "5") (pinfunction "5_5") (pintype "passive"))
      (node (ref "JP5") (pin "6") (pinfunction "6_6") (pintype "passive"))
      (node (ref "JP5") (pin "7") (pinfunction "7_7") (pintype "passive"))
      (node (ref "JP5") (pin "8") (pinfunction "8_8") (pintype "passive"))
      (node (ref "R15") (pin "1") (pinfunction "1_1") (pintype "passive"))
      (node (ref "R27") (pin "1") (pinfunction "1_1") (pintype "passive"))
      (node (ref "R29") (pin "P$3") (pinfunction "A_P$3") (pintype "passive"))
      (node (ref "R3") (pin "P$3") (pinfunction "A_P$3") (pintype "passive"))
      (node (ref "R35") (pin "1") (pinfunction "1_1") (pintype "passive"))
      (node (ref "R38") (pin "2") (pinfunction "2_2") (pintype "passive"))
      (node (ref "R42") (pin "P$3") (pinfunction "A_P$3") (pintype "passive"))
      (node (ref "R45") (pin "2") (pinfunction "2_2") (pintype "passive"))
      (node (ref "R47") (pin "1") (pinfunction "1_1") (pintype "passive"))
      (node (ref "R55") (pin "1") (pinfunction "1_1") (pintype "passive"))
      (node (ref "R6") (pin "2") (pinfunction "2_2") (pintype "passive"))
      (node (ref "R68") (pin "1") (pinfunction "1_1") (pintype "passive"))
      (node (ref "R70") (pin "P$3") (pinfunction "A_P$3") (pintype "passive"))
      (node (ref "R77") (pin "1") (pinfunction "1_1") (pintype "passive"))
      (node (ref "R78") (pin "2") (pinfunction "2_2") (pintype "passive"))
      (node (ref "R8") (pin "1") (pinfunction "1_1") (pintype "passive"))
    )
    (net (code "7") (name "Net-(C9-Pad1)") (class "Default")
      (node (ref "C9") (pin "1") (pinfunction "1_1") (pintype "passive"))
      (node (ref "R13") (pin "1") (pinfunction "1_1") (pintype "passive"))
    )
    (net (code "8") (name "Net-(C10-Pad1)") (class "Default")
      (node (ref "C10") (pin "1") (pinfunction "1_1") (pintype "passive"))
      (node (ref "R18") (pin "1") (pinfunction "1_1") (pintype "passive"))
    )
    (net (code "9") (name "Net-(C13-Pad1)") (class "Default")
      (node (ref "C13") (pin "1") (pinfunction "1_1") (pintype "passive"))
      (node (ref "R21") (pin "1") (pinfunction "1_1") (pintype "passive"))
    )
    (net (code "10") (name "Net-(C14-Pad1)") (class "Default")
      (node (ref "C14") (pin "1") (pinfunction "1_1") (pintype "passive"))
      (node (ref "R24") (pin "1") (pinfunction "1_1") (pintype "passive"))
    )
    (net (code "11") (name "Net-(C29-Pad1)") (class "Default")
      (node (ref "C29") (pin "1") (pinfunction "1_1") (pintype "passive"))
      (node (ref "R53") (pin "1") (pinfunction "1_1") (pintype "passive"))
    )
    (net (code "12") (name "Net-(C30-Pad1)") (class "Default")
      (node (ref "C30") (pin "1") (pinfunction "1_1") (pintype "passive"))
      (node (ref "R58") (pin "1") (pinfunction "1_1") (pintype "passive"))
    )
    (net (code "13") (name "Net-(C33-Pad1)") (class "Default")
      (node (ref "C33") (pin "1") (pinfunction "1_1") (pintype "passive"))
      (node (ref "R61") (pin "1") (pinfunction "1_1") (pintype "passive"))
    )
    (net (code "14") (name "Net-(C34-Pad1)") (class "Default")
      (node (ref "C34") (pin "1") (pinfunction "1_1") (pintype "passive"))
      (node (ref "R65") (pin "1") (pinfunction "1_1") (pintype "passive"))
    )
    (net (code "15") (name "Net-(D2-PadA)") (class "Default")
      (node (ref "D2") (pin "A") (pinfunction "A_A") (pintype "passive"))
      (node (ref "JP5") (pin "1") (pinfunction "1_1") (pintype "passive"))
      (node (ref "JP5") (pin "2") (pinfunction "2_2") (pintype "passive"))
    )
    (net (code "16") (name "Net-(D2-PadC)") (class "Default")
      (node (ref "D2") (pin "C") (pinfunction "C_C") (pintype "passive"))
      (node (ref "L2") (pin "2") (pinfunction "2_2") (pintype "passive"))
    )
    (net (code "17") (name "Net-(IC1A--IN)") (class "Default")
      (node (ref "C5") (pin "1") (pinfunction "1_1") (pintype "passive"))
      (node (ref "IC1") (pin "2") (pinfunction "-IN_2") (pintype "input"))
      (node (ref "IC3") (pin "4") (pinfunction "OUT_4") (pintype "output"))
      (node (ref "R19") (pin "1") (pinfunction "1_1") (pintype "passive"))
      (node (ref "R3") (pin "P$1") (pinfunction "E_P$1") (pintype "passive"))
    )
    (net (code "18") (name "Net-(IC1A-OUT)") (class "Default")
      (node (ref "C5") (pin "2") (pinfunction "2_2") (pintype "passive"))
      (node (ref "IC1") (pin "1") (pinfunction "OUT_1") (pintype "output"))
      (node (ref "IC3") (pin "14") (pinfunction "CTRL_14") (pintype "input"))
      (node (ref "R1") (pin "P$1") (pinfunction "E_P$1") (pintype "passive"))
    )
    (net (code "19") (name "Net-(IC1B--IN)") (class "Default")
      (node (ref "C41") (pin "1") (pinfunction "1_1") (pintype "passive"))
      (node (ref "IC1") (pin "6") (pinfunction "-IN_6") (pintype "input"))
      (node (ref "IC3") (pin "13") (pinfunction "OUT_13") (pintype "output"))
      (node (ref "R7") (pin "2") (pinfunction "2_2") (pintype "passive"))
    )
    (net (code "20") (name "Net-(IC1B-OUT)") (class "Default")
      (node (ref "C41") (pin "2") (pinfunction "2_2") (pintype "passive"))
      (node (ref "IC1") (pin "7") (pinfunction "OUT_7") (pintype "output"))
      (node (ref "R7") (pin "1") (pinfunction "1_1") (pintype "passive"))
      (node (ref "R9") (pin "2") (pinfunction "2_2") (pintype "passive"))
    )
    (net (code "21") (name "Net-(IC1C--IN)") (class "Default")
      (node (ref "C6") (pin "1") (pinfunction "1_1") (pintype "passive"))
      (node (ref "IC1") (pin "9") (pinfunction "-IN_9") (pintype "input"))
      (node (ref "R10") (pin "2") (pinfunction "2_2") (pintype "passive"))
      (node (ref "R9") (pin "1") (pinfunction "1_1") (pintype "passive"))
    )
    (net (code "22") (name "Net-(IC1C-OUT)") (class "Default")
      (node (ref "C6") (pin "2") (pinfunction "2_2") (pintype "passive"))
      (node (ref "IC1") (pin "8") (pinfunction "OUT_8") (pintype "output"))
      (node (ref "R10") (pin "1") (pinfunction "1_1") (pintype "passive"))
      (node (ref "R12") (pin "1") (pinfunction "1_1") (pintype "passive"))
      (node (ref "R2") (pin "2") (pinfunction "2_2") (pintype "passive"))
    )
    (net (code "23") (name "Net-(IC1D--IN)") (class "Default")
      (node (ref "IC1") (pin "13") (pinfunction "-IN_13") (pintype "input"))
      (node (ref "R4") (pin "2") (pinfunction "2_2") (pintype "passive"))
      (node (ref "R5") (pin "1") (pinfunction "1_1") (pintype "passive"))
    )
    (net (code "24") (name "Net-(IC2A-+IN)") (class "Default")
      (node (ref "IC2") (pin "3") (pinfunction "+IN_3") (pintype "input"))
      (node (ref "R12") (pin "2") (pinfunction "2_2") (pintype "passive"))
      (node (ref "R15") (pin "2") (pinfunction "2_2") (pintype "passive"))
    )
    (net (code "25") (name "Net-(IC2A--IN)") (class "Default")
      (node (ref "IC2") (pin "2") (pinfunction "-IN_2") (pintype "input"))
      (node (ref "LED1") (pin "A") (pinfunction "A_A") (pintype "passive"))
      (node (ref "R6") (pin "1") (pinfunction "1_1") (pintype "passive"))
    )
    (net (code "26") (name "Net-(IC2A-OUT)") (class "Default")
      (node (ref "IC2") (pin "1") (pinfunction "OUT_1") (pintype "output"))
      (node (ref "LED1") (pin "K") (pinfunction "C_K") (pintype "passive"))
    )
    (net (code "27") (name "Net-(IC2B-+IN)") (class "Default")
      (node (ref "IC2") (pin "5") (pinfunction "+IN_5") (pintype "input"))
      (node (ref "R26") (pin "2") (pinfunction "2_2") (pintype "passive"))
      (node (ref "R27") (pin "2") (pinfunction "2_2") (pintype "passive"))
    )
    (net (code "28") (name "Net-(IC2B--IN)") (class "Default")
      (node (ref "IC2") (pin "6") (pinfunction "-IN_6") (pintype "input"))
      (node (ref "LED2") (pin "A") (pinfunction "A_A") (pintype "passive"))
      (node (ref "R38") (pin "1") (pinfunction "1_1") (pintype "passive"))
    )
    (net (code "29") (name "Net-(IC2B-OUT)") (class "Default")
      (node (ref "IC2") (pin "7") (pinfunction "OUT_7") (pintype "output"))
      (node (ref "LED2") (pin "K") (pinfunction "C_K") (pintype "passive"))
    )
    (net (code "30") (name "Net-(IC3A-CTRL)") (class "Default")
      (node (ref "IC3") (pin "3") (pinfunction "CTRL_3") (pintype "input"))
      (node (ref "R1") (pin "P$2") (pinfunction "S_P$2") (pintype "passive"))
    )
    (net (code "31") (name "Net-(IC3A-IN)") (class "Default")
      (node (ref "IC3") (pin "2") (pinfunction "IN_2") (pintype "input"))
      (node (ref "R13") (pin "2") (pinfunction "2_2") (pintype "passive"))
      (node (ref "R17") (pin "1") (pinfunction "1_1") (pintype "passive"))
    )
    (net (code "32") (name "Net-(IC3B-CTRL)") (class "Default")
      (node (ref "IC3") (pin "6") (pinfunction "CTRL_6") (pintype "input"))
      (node (ref "R28") (pin "P$2") (pinfunction "S_P$2") (pintype "passive"))
    )
    (net (code "33") (name "Net-(IC3B-IN)") (class "Default")
      (node (ref "IC3") (pin "7") (pinfunction "IN_7") (pintype "input"))
      (node (ref "R23") (pin "1") (pinfunction "1_1") (pintype "passive"))
      (node (ref "R24") (pin "2") (pinfunction "2_2") (pintype "passive"))
    )
    (net (code "34") (name "Net-(IC3B-OUT)") (class "Default")
      (node (ref "C18") (pin "1") (pinfunction "1_1") (pintype "passive"))
      (node (ref "IC3") (pin "5") (pinfunction "OUT_5") (pintype "output"))
      (node (ref "IC4") (pin "6") (pinfunction "-IN_6") (pintype "input"))
      (node (ref "R20") (pin "1") (pinfunction "1_1") (pintype "passive"))
      (node (ref "R29") (pin "P$1") (pinfunction "E_P$1") (pintype "passive"))
    )
    (net (code "35") (name "Net-(IC3C-CTRL)") (class "Default")
      (node (ref "C18") (pin "2") (pinfunction "2_2") (pintype "passive"))
      (node (ref "IC3") (pin "11") (pinfunction "CTRL_11") (pintype "input"))
      (node (ref "IC4") (pin "7") (pinfunction "OUT_7") (pintype "output"))
      (node (ref "R28") (pin "P$1") (pinfunction "E_P$1") (pintype "passive"))
    )
    (net (code "36") (name "Net-(IC3C-IN)") (class "Default")
      (node (ref "IC3") (pin "10") (pinfunction "IN_10") (pintype "input"))
      (node (ref "R21") (pin "2") (pinfunction "2_2") (pintype "passive"))
      (node (ref "R25") (pin "1") (pinfunction "1_1") (pintype "passive"))
    )
    (net (code "37") (name "Net-(IC3C-OUT)") (class "Default")
      (node (ref "C42") (pin "1") (pinfunction "1_1") (pintype "passive"))
      (node (ref "IC3") (pin "12") (pinfunction "OUT_12") (pintype "output"))
      (node (ref "IC4") (pin "2") (pinfunction "-IN_2") (pintype "input"))
      (node (ref "R33") (pin "2") (pinfunction "2_2") (pintype "passive"))
    )
    (net (code "38") (name "Net-(IC3D-IN)") (class "Default")
      (node (ref "IC3") (pin "15") (pinfunction "IN_15") (pintype "input"))
      (node (ref "R14") (pin "1") (pinfunction "1_1") (pintype "passive"))
      (node (ref "R18") (pin "2") (pinfunction "2_2") (pintype "passive"))
    )
    (net (code "39") (name "Net-(IC4A-OUT)") (class "Default")
      (node (ref "C42") (pin "2") (pinfunction "2_2") (pintype "passive"))
      (node (ref "IC4") (pin "1") (pinfunction "OUT_1") (pintype "output"))
      (node (ref "R32") (pin "2") (pinfunction "2_2") (pintype "passive"))
      (node (ref "R33") (pin "1") (pinfunction "1_1") (pintype "passive"))
    )
    (net (code "40") (name "Net-(IC4C--IN)") (class "Default")
      (node (ref "IC4") (pin "9") (pinfunction "-IN_9") (pintype "input"))
      (node (ref "R34") (pin "1") (pinfunction "1_1") (pintype "passive"))
      (node (ref "R36") (pin "2") (pinfunction "2_2") (pintype "passive"))
    )
    (net (code "41") (name "Net-(IC4D--IN)") (class "Default")
      (node (ref "C17") (pin "1") (pinfunction "1_1") (pintype "passive"))
      (node (ref "IC4") (pin "13") (pinfunction "-IN_13") (pintype "input"))
      (node (ref "R30") (pin "1") (pinfunction "1_1") (pintype "passive"))
      (node (ref "R31") (pin "2") (pinfunction "2_2") (pintype "passive"))
      (node (ref "R32") (pin "1") (pinfunction "1_1") (pintype "passive"))
    )
    (net (code "42") (name "Net-(IC4D-OUT)") (class "Default")
      (node (ref "C17") (pin "2") (pinfunction "2_2") (pintype "passive"))
      (node (ref "IC4") (pin "14") (pinfunction "OUT_14") (pintype "output"))
      (node (ref "R22") (pin "2") (pinfunction "2_2") (pintype "passive"))
      (node (ref "R26") (pin "1") (pinfunction "1_1") (pintype "passive"))
      (node (ref "R31") (pin "1") (pinfunction "1_1") (pintype "passive"))
    )
    (net (code "43") (name "Net-(IC5A--IN)") (class "Default")
      (node (ref "C25") (pin "1") (pinfunction "1_1") (pintype "passive"))
      (node (ref "IC5") (pin "2") (pinfunction "-IN_2") (pintype "input"))
      (node (ref "IC7") (pin "4") (pinfunction "OUT_4") (pintype "output"))
      (node (ref "R42") (pin "P$1") (pinfunction "E_P$1") (pintype "passive"))
      (node (ref "R59") (pin "1") (pinfunction "1_1") (pintype "passive"))
    )
    (net (code "44") (name "Net-(IC5A-OUT)") (class "Default")
      (node (ref "C25") (pin "2") (pinfunction "2_2") (pintype "passive"))
      (node (ref "IC5") (pin "1") (pinfunction "OUT_1") (pintype "output"))
      (node (ref "IC7") (pin "14") (pinfunction "CTRL_14") (pintype "input"))
      (node (ref "R40") (pin "P$1") (pinfunction "E_P$1") (pintype "passive"))
    )
    (net (code "45") (name "Net-(IC5B--IN)") (class "Default")
      (node (ref "C43") (pin "1") (pinfunction "1_1") (pintype "passive"))
      (node (ref "IC5") (pin "6") (pinfunction "-IN_6") (pintype "input"))
      (node (ref "IC7") (pin "13") (pinfunction "OUT_13") (pintype "output"))
      (node (ref "R46") (pin "2") (pinfunction "2_2") (pintype "passive"))
    )
    (net (code "46") (name "Net-(IC5B-OUT)") (class "Default")
      (node (ref "C43") (pin "2") (pinfunction "2_2") (pintype "passive"))
      (node (ref "IC5") (pin "7") (pinfunction "OUT_7") (pintype "output"))
      (node (ref "R46") (pin "1") (pinfunction "1_1") (pintype "passive"))
      (node (ref "R49") (pin "2") (pinfunction "2_2") (pintype "passive"))
    )
    (net (code "47") (name "Net-(IC5C--IN)") (class "Default")
      (node (ref "C26") (pin "1") (pinfunction "1_1") (pintype "passive"))
      (node (ref "IC5") (pin "9") (pinfunction "-IN_9") (pintype "input"))
      (node (ref "R48") (pin "1") (pinfunction "1_1") (pintype "passive"))
      (node (ref "R49") (pin "1") (pinfunction "1_1") (pintype "passive"))
      (node (ref "R50") (pin "2") (pinfunction "2_2") (pintype "passive"))
    )
    (net (code "48") (name "Net-(IC5C-OUT)") (class "Default")
      (node (ref "C26") (pin "2") (pinfunction "2_2") (pintype "passive"))
      (node (ref "IC5") (pin "8") (pinfunction "OUT_8") (pintype "output"))
      (node (ref "R41") (pin "2") (pinfunction "2_2") (pintype "passive"))
      (node (ref "R50") (pin "1") (pinfunction "1_1") (pintype "passive"))
      (node (ref "R52") (pin "1") (pinfunction "1_1") (pintype "passive"))
    )
    (net (code "49") (name "Net-(IC5D--IN)") (class "Default")
      (node (ref "IC5") (pin "13") (pinfunction "-IN_13") (pintype "input"))
      (node (ref "R43") (pin "2") (pinfunction "2_2") (pintype "passive"))
      (node (ref "R44") (pin "1") (pinfunction "1_1") (pintype "passive"))
    )
    (net (code "50") (name "Net-(IC6A-+IN)") (class "Default")
      (node (ref "IC6") (pin "3") (pinfunction "+IN_3") (pintype "input"))
      (node (ref "R52") (pin "2") (pinfunction "2_2") (pintype "passive"))
      (node (ref "R55") (pin "2") (pinfunction "2_2") (pintype "passive"))
    )
    (net (code "51") (name "Net-(IC6A--IN)") (class "Default")
      (node (ref "IC6") (pin "2") (pinfunction "-IN_2") (pintype "input"))
      (node (ref "LED3") (pin "A") (pinfunction "A_A") (pintype "passive"))
      (node (ref "R45") (pin "1") (pinfunction "1_1") (pintype "passive"))
    )
    (net (code "52") (name "Net-(IC6A-OUT)") (class "Default")
      (node (ref "IC6") (pin "1") (pinfunction "OUT_1") (pintype "output"))
      (node (ref "LED3") (pin "K") (pinfunction "C_K") (pintype "passive"))
    )
    (net (code "53") (name "Net-(IC6B-+IN)") (class "Default")
      (node (ref "IC6") (pin "5") (pinfunction "+IN_5") (pintype "input"))
      (node (ref "R67") (pin "2") (pinfunction "2_2") (pintype "passive"))
      (node (ref "R68") (pin "2") (pinfunction "2_2") (pintype "passive"))
    )
    (net (code "54") (name "Net-(IC6B--IN)") (class "Default")
      (node (ref "IC6") (pin "6") (pinfunction "-IN_6") (pintype "input"))
      (node (ref "LED4") (pin "A") (pinfunction "A_A") (pintype "passive"))
      (node (ref "R78") (pin "1") (pinfunction "1_1") (pintype "passive"))
    )
    (net (code "55") (name "Net-(IC6B-OUT)") (class "Default")
      (node (ref "IC6") (pin "7") (pinfunction "OUT_7") (pintype "output"))
      (node (ref "LED4") (pin "K") (pinfunction "C_K") (pintype "passive"))
    )
    (net (code "56") (name "Net-(IC7A-CTRL)") (class "Default")
      (node (ref "IC7") (pin "3") (pinfunction "CTRL_3") (pintype "input"))
      (node (ref "R40") (pin "P$2") (pinfunction "S_P$2") (pintype "passive"))
    )
    (net (code "57") (name "Net-(IC7A-IN)") (class "Default")
      (node (ref "IC7") (pin "2") (pinfunction "IN_2") (pintype "input"))
      (node (ref "R53") (pin "2") (pinfunction "2_2") (pintype "passive"))
      (node (ref "R57") (pin "1") (pinfunction "1_1") (pintype "passive"))
    )
    (net (code "58") (name "Net-(IC7B-CTRL)") (class "Default")
      (node (ref "IC7") (pin "6") (pinfunction "CTRL_6") (pintype "input"))
      (node (ref "R69") (pin "P$2") (pinfunction "S_P$2") (pintype "passive"))
    )
    (net (code "59") (name "Net-(IC7B-IN)") (class "Default")
      (node (ref "IC7") (pin "7") (pinfunction "IN_7") (pintype "input"))
      (node (ref "R63") (pin "1") (pinfunction "1_1") (pintype "passive"))
      (node (ref "R65") (pin "2") (pinfunction "2_2") (pintype "passive"))
    )
    (net (code "60") (name "Net-(IC7C-IN)") (class "Default")
      (node (ref "IC7") (pin "10") (pinfunction "IN_10") (pintype "input"))
      (node (ref "R61") (pin "2") (pinfunction "2_2") (pintype "passive"))
      (node (ref "R66") (pin "1") (pinfunction "1_1") (pintype "passive"))
    )
    (net (code "61") (name "Net-(IC7D-IN)") (class "Default")
      (node (ref "IC7") (pin "15") (pinfunction "IN_15") (pintype "input"))
      (node (ref "R54") (pin "1") (pinfunction "1_1") (pintype "passive"))
      (node (ref "R58") (pin "2") (pinfunction "2_2") (pintype "passive"))
    )
    (net (code "62") (name "Net-(IC10A--IN)") (class "Default")
      (node (ref "C44") (pin "1") (pinfunction "1_1") (pintype "passive"))
      (node (ref "IC10") (pin "2") (pinfunction "-IN_2") (pintype "input"))
      (node (ref "IC7") (pin "12") (pinfunction "OUT_12") (pintype "output"))
      (node (ref "R76") (pin "2") (pinfunction "2_2") (pintype "passive"))
    )
    (net (code "63") (name "Net-(IC10A-OUT)") (class "Default")
      (node (ref "C44") (pin "2") (pinfunction "2_2") (pintype "passive"))
      (node (ref "IC10") (pin "1") (pinfunction "OUT_1") (pintype "output"))
      (node (ref "R75") (pin "2") (pinfunction "2_2") (pintype "passive"))
      (node (ref "R76") (pin "1") (pinfunction "1_1") (pintype "passive"))
    )
    (net (code "64") (name "Net-(IC10B--IN)") (class "Default")
      (node (ref "C38") (pin "1") (pinfunction "1_1") (pintype "passive"))
      (node (ref "IC10") (pin "6") (pinfunction "-IN_6") (pintype "input"))
      (node (ref "IC7") (pin "5") (pinfunction "OUT_5") (pintype "output"))
      (node (ref "R60") (pin "1") (pinfunction "1_1") (pintype "passive"))
      (node (ref "R70") (pin "P$1") (pinfunction "E_P$1") (pintype "passive"))
    )
    (net (code "65") (name "Net-(IC10B-OUT)") (class "Default")
      (node (ref "C38") (pin "2") (pinfunction "2_2") (pintype "passive"))
      (node (ref "IC10") (pin "7") (pinfunction "OUT_7") (pintype "output"))
      (node (ref "IC7") (pin "11") (pinfunction "CTRL_11") (pintype "input"))
      (node (ref "R69") (pin "P$1") (pinfunction "E_P$1") (pintype "passive"))
    )
    (net (code "66") (name "Net-(IC10C--IN)") (class "Default")
      (node (ref "IC10") (pin "8") (pinfunction "OUT_8") (pintype "output"))
      (node (ref "IC10") (pin "9") (pinfunction "-IN_9") (pintype "input"))
    )
    (net (code "67") (name "Net-(IC10D--IN)") (class "Default")
      (node (ref "C37") (pin "1") (pinfunction "1_1") (pintype "passive"))
      (node (ref "IC10") (pin "13") (pinfunction "-IN_13") (pintype "input"))
      (node (ref "R71") (pin "1") (pinfunction "1_1") (pintype "passive"))
      (node (ref "R73") (pin "2") (pinfunction "2_2") (pintype "passive"))
      (node (ref "R75") (pin "1") (pinfunction "1_1") (pintype "passive"))
    )
    (net (code "68") (name "Net-(IC10D-OUT)") (class "Default")
      (node (ref "C37") (pin "2") (pinfunction "2_2") (pintype "passive"))
      (node (ref "IC10") (pin "14") (pinfunction "OUT_14") (pintype "output"))
      (node (ref "R62") (pin "2") (pinfunction "2_2") (pintype "passive"))
      (node (ref "R67") (pin "1") (pinfunction "1_1") (pintype "passive"))
      (node (ref "R73") (pin "1") (pinfunction "1_1") (pintype "passive"))
    )
    (net (code "69") (name "Net-(J1-3)") (class "Default")
      (node (ref "J1") (pin "P3") (pinfunction "3_P3") (pintype "passive"))
      (node (ref "R14") (pin "2") (pinfunction "2_2") (pintype "passive"))
    )
    (net (code "70") (name "Net-(J2-2)") (class "Default")
      (node (ref "J2") (pin "P2") (pinfunction "2_P2") (pintype "passive"))
      (node (ref "R5") (pin "2") (pinfunction "2_2") (pintype "passive"))
    )
    (net (code "71") (name "Net-(J2-3)") (class "Default")
      (node (ref "J2") (pin "P3") (pinfunction "3_P3") (pintype "passive"))
      (node (ref "R2") (pin "1") (pinfunction "1_1") (pintype "passive"))
    )
    (net (code "72") (name "Net-(J3-2)") (class "Default")
      (node (ref "J3") (pin "P2") (pinfunction "2_P2") (pintype "passive"))
      (node (ref "R16") (pin "1") (pinfunction "1_1") (pintype "passive"))
    )
    (net (code "73") (name "Net-(J3-3)") (class "Default")
      (node (ref "J3") (pin "P3") (pinfunction "3_P3") (pintype "passive"))
      (node (ref "R11") (pin "2") (pinfunction "2_2") (pintype "passive"))
    )
    (net (code "74") (name "Net-(J4-3)") (class "Default")
      (node (ref "J4") (pin "P3") (pinfunction "3_P3") (pintype "passive"))
      (node (ref "R25") (pin "2") (pinfunction "2_2") (pintype "passive"))
    )
    (net (code "75") (name "Net-(J5-2)") (class "Default")
      (node (ref "J5") (pin "P2") (pinfunction "2_P2") (pintype "passive"))
      (node (ref "R34") (pin "2") (pinfunction "2_2") (pintype "passive"))
    )
    (net (code "76") (name "Net-(J5-3)") (class "Default")
      (node (ref "J5") (pin "P3") (pinfunction "3_P3") (pintype "passive"))
      (node (ref "R22") (pin "1") (pinfunction "1_1") (pintype "passive"))
    )
    (net (code "77") (name "Net-(J6-2)") (class "Default")
      (node (ref "J6") (pin "P2") (pinfunction "2_P2") (pintype "passive"))
      (node (ref "R39") (pin "1") (pinfunction "1_1") (pintype "passive"))
    )
    (net (code "78") (name "Net-(J6-3)") (class "Default")
      (node (ref "J6") (pin "P3") (pinfunction "3_P3") (pintype "passive"))
      (node (ref "R37") (pin "2") (pinfunction "2_2") (pintype "passive"))
    )
    (net (code "79") (name "Net-(J7-3)") (class "Default")
      (node (ref "J7") (pin "P3") (pinfunction "3_P3") (pintype "passive"))
      (node (ref "R54") (pin "2") (pinfunction "2_2") (pintype "passive"))
    )
    (net (code "80") (name "Net-(J8-2)") (class "Default")
      (node (ref "J8") (pin "P2") (pinfunction "2_P2") (pintype "passive"))
      (node (ref "R44") (pin "2") (pinfunction "2_2") (pintype "passive"))
    )
    (net (code "81") (name "Net-(J8-3)") (class "Default")
      (node (ref "J8") (pin "P3") (pinfunction "3_P3") (pintype "passive"))
      (node (ref "R41") (pin "1") (pinfunction "1_1") (pintype "passive"))
    )
    (net (code "82") (name "Net-(J9-2)") (class "Default")
      (node (ref "J9") (pin "P2") (pinfunction "2_P2") (pintype "passive"))
      (node (ref "R56") (pin "1") (pinfunction "1_1") (pintype "passive"))
    )
    (net (code "83") (name "Net-(J9-3)") (class "Default")
      (node (ref "J9") (pin "P3") (pinfunction "3_P3") (pintype "passive"))
      (node (ref "R51") (pin "2") (pinfunction "2_2") (pintype "passive"))
    )
    (net (code "84") (name "Net-(J10-3)") (class "Default")
      (node (ref "J10") (pin "P3") (pinfunction "3_P3") (pintype "passive"))
      (node (ref "R66") (pin "2") (pinfunction "2_2") (pintype "passive"))
    )
    (net (code "85") (name "Net-(J11-3)") (class "Default")
      (node (ref "J11") (pin "P3") (pinfunction "3_P3") (pintype "passive"))
      (node (ref "R62") (pin "1") (pinfunction "1_1") (pintype "passive"))
    )
    (net (code "86") (name "Net-(J12-2)") (class "Default")
      (node (ref "J12") (pin "P2") (pinfunction "2_P2") (pintype "passive"))
      (node (ref "R72") (pin "1") (pinfunction "1_1") (pintype "passive"))
    )
    (net (code "87") (name "Net-(J12-3)") (class "Default")
      (node (ref "J12") (pin "P3") (pinfunction "3_P3") (pintype "passive"))
      (node (ref "R79") (pin "2") (pinfunction "2_2") (pintype "passive"))
    )
    (net (code "88") (name "Net-(JP5-Pad10)") (class "Default")
      (node (ref "JP5") (pin "10") (pinfunction "10_10") (pintype "passive"))
      (node (ref "JP5") (pin "9") (pinfunction "9_9") (pintype "passive"))
      (node (ref "P1") (pin "2") (pinfunction "2_2") (pintype "bidirectional"))
    )
    (net (code "89") (name "Net-(L1-Pad2)") (class "Default")
      (node (ref "L1") (pin "2") (pinfunction "2_2") (pintype "passive"))
      (node (ref "P1") (pin "1") (pinfunction "1_1") (pintype "bidirectional"))
    )
    (net (code "90") (name "Net-(R1-A)") (class "Default")
      (node (ref "R1") (pin "P$3") (pinfunction "A_P$3") (pintype "passive"))
      (node (ref "R8") (pin "2") (pinfunction "2_2") (pintype "passive"))
    )
    (net (code "91") (name "Net-(R3-S)") (class "Default")
      (node (ref "R11") (pin "1") (pinfunction "1_1") (pintype "passive"))
      (node (ref "R3") (pin "P$2") (pinfunction "S_P$2") (pintype "passive"))
    )
    (net (code "92") (name "Net-(R28-A)") (class "Default")
      (node (ref "R28") (pin "P$3") (pinfunction "A_P$3") (pintype "passive"))
      (node (ref "R35") (pin "2") (pinfunction "2_2") (pintype "passive"))
    )
    (net (code "93") (name "Net-(R29-S)") (class "Default")
      (node (ref "R29") (pin "P$2") (pinfunction "S_P$2") (pintype "passive"))
      (node (ref "R37") (pin "1") (pinfunction "1_1") (pintype "passive"))
    )
    (net (code "94") (name "Net-(R40-A)") (class "Default")
      (node (ref "R40") (pin "P$3") (pinfunction "A_P$3") (pintype "passive"))
      (node (ref "R47") (pin "2") (pinfunction "2_2") (pintype "passive"))
    )
    (net (code "95") (name "Net-(R42-S)") (class "Default")
      (node (ref "R42") (pin "P$2") (pinfunction "S_P$2") (pintype "passive"))
      (node (ref "R51") (pin "1") (pinfunction "1_1") (pintype "passive"))
    )
    (net (code "96") (name "Net-(R69-A)") (class "Default")
      (node (ref "R69") (pin "P$3") (pinfunction "A_P$3") (pintype "passive"))
      (node (ref "R77") (pin "2") (pinfunction "2_2") (pintype "passive"))
    )
    (net (code "97") (name "Net-(R70-S)") (class "Default")
      (node (ref "R70") (pin "P$2") (pinfunction "S_P$2") (pintype "passive"))
      (node (ref "R79") (pin "1") (pinfunction "1_1") (pintype "passive"))
    )
    (net (code "98") (name "VCC") (class "Default")
      (node (ref "C19") (pin "1") (pinfunction "1_1") (pintype "passive"))
      (node (ref "C2") (pin "+") (pinfunction "+_+") (pintype "passive"))
      (node (ref "C21") (pin "+") (pinfunction "+_+") (pintype "passive"))
      (node (ref "C24") (pin "1") (pinfunction "1_1") (pintype "passive"))
      (node (ref "C27") (pin "1") (pinfunction "1_1") (pintype "passive"))
      (node (ref "C28") (pin "1") (pinfunction "1_1") (pintype "passive"))
      (node (ref "C4") (pin "1") (pinfunction "1_1") (pintype "passive"))
      (node (ref "C40") (pin "1") (pinfunction "1_1") (pintype "passive"))
      (node (ref "C7") (pin "1") (pinfunction "1_1") (pintype "passive"))
      (node (ref "C8") (pin "1") (pinfunction "1_1") (pintype "passive"))
      (node (ref "IC1") (pin "4") (pinfunction "V+_4") (pintype "power_in"))
      (node (ref "IC10") (pin "4") (pinfunction "V+_4") (pintype "power_in"))
      (node (ref "IC2") (pin "8") (pinfunction "V+_8") (pintype "power_in"))
      (node (ref "IC3") (pin "16") (pinfunction "V+_16") (pintype "power_in"))
      (node (ref "IC4") (pin "4") (pinfunction "V+_4") (pintype "power_in"))
      (node (ref "IC5") (pin "4") (pinfunction "V+_4") (pintype "power_in"))
      (node (ref "IC6") (pin "8") (pinfunction "V+_8") (pintype "power_in"))
      (node (ref "IC7") (pin "16") (pinfunction "V+_16") (pintype "power_in"))
      (node (ref "L2") (pin "1") (pinfunction "1_1") (pintype "passive"))
      (node (ref "R74") (pin "1") (pinfunction "1_1") (pintype "passive"))
    )
    (net (code "99") (name "VEE") (class "Default")
      (node (ref "C1") (pin "-") (pinfunction "-_-") (pintype "passive"))
      (node (ref "C11") (pin "2") (pinfunction "2_2") (pintype "passive"))
      (node (ref "C15") (pin "2") (pinfunction "2_2") (pintype "passive"))
      (node (ref "C20") (pin "2") (pinfunction "2_2") (pintype "passive"))
      (node (ref "C22") (pin "-") (pinfunction "-_-") (pintype "passive"))
      (node (ref "C23") (pin "2") (pinfunction "2_2") (pintype "passive"))
      (node (ref "C3") (pin "2") (pinfunction "2_2") (pintype "passive"))
      (node (ref "C31") (pin "2") (pinfunction "2_2") (pintype "passive"))
      (node (ref "C35") (pin "2") (pinfunction "2_2") (pintype "passive"))
      (node (ref "C39") (pin "2") (pinfunction "2_2") (pintype "passive"))
      (node (ref "D1") (pin "A") (pinfunction "A_A") (pintype "passive"))
      (node (ref "IC1") (pin "11") (pinfunction "V-_11") (pintype "power_in"))
      (node (ref "IC10") (pin "11") (pinfunction "V-_11") (pintype "power_in"))
      (node (ref "IC2") (pin "4") (pinfunction "V-_4") (pintype "power_in"))
      (node (ref "IC3") (pin "9") (pinfunction "V-_9") (pintype "power_in"))
      (node (ref "IC4") (pin "11") (pinfunction "V-_11") (pintype "power_in"))
      (node (ref "IC5") (pin "11") (pinfunction "V-_11") (pintype "power_in"))
      (node (ref "IC6") (pin "4") (pinfunction "V-_4") (pintype "power_in"))
      (node (ref "IC7") (pin "9") (pinfunction "V-_9") (pintype "power_in"))
      (node (ref "L1") (pin "1") (pinfunction "1_1") (pintype "passive"))
      (node (ref "R64") (pin "1") (pinfunction "1_1") (pintype "passive"))
    )
    (net (code "100") (name "unconnected-(IC3E-MODE-Pad1)") (class "Default")
      (node (ref "IC3") (pin "1") (pinfunction "MODE_1") (pintype "input"))
    )
    (net (code "101") (name "unconnected-(IC7E-MODE-Pad1)") (class "Default")
      (node (ref "IC7") (pin "1") (pinfunction "MODE_1") (pintype "input"))
    )
    (net (code "102") (name "unconnected-(J11-2-PadP2)") (class "Default")
      (node (ref "J11") (pin "P2") (pinfunction "2_P2") (pintype "passive"))
    )
  )
)
